# homeboard12.net
KiCad netlist of a schematic drawn in EAGLE
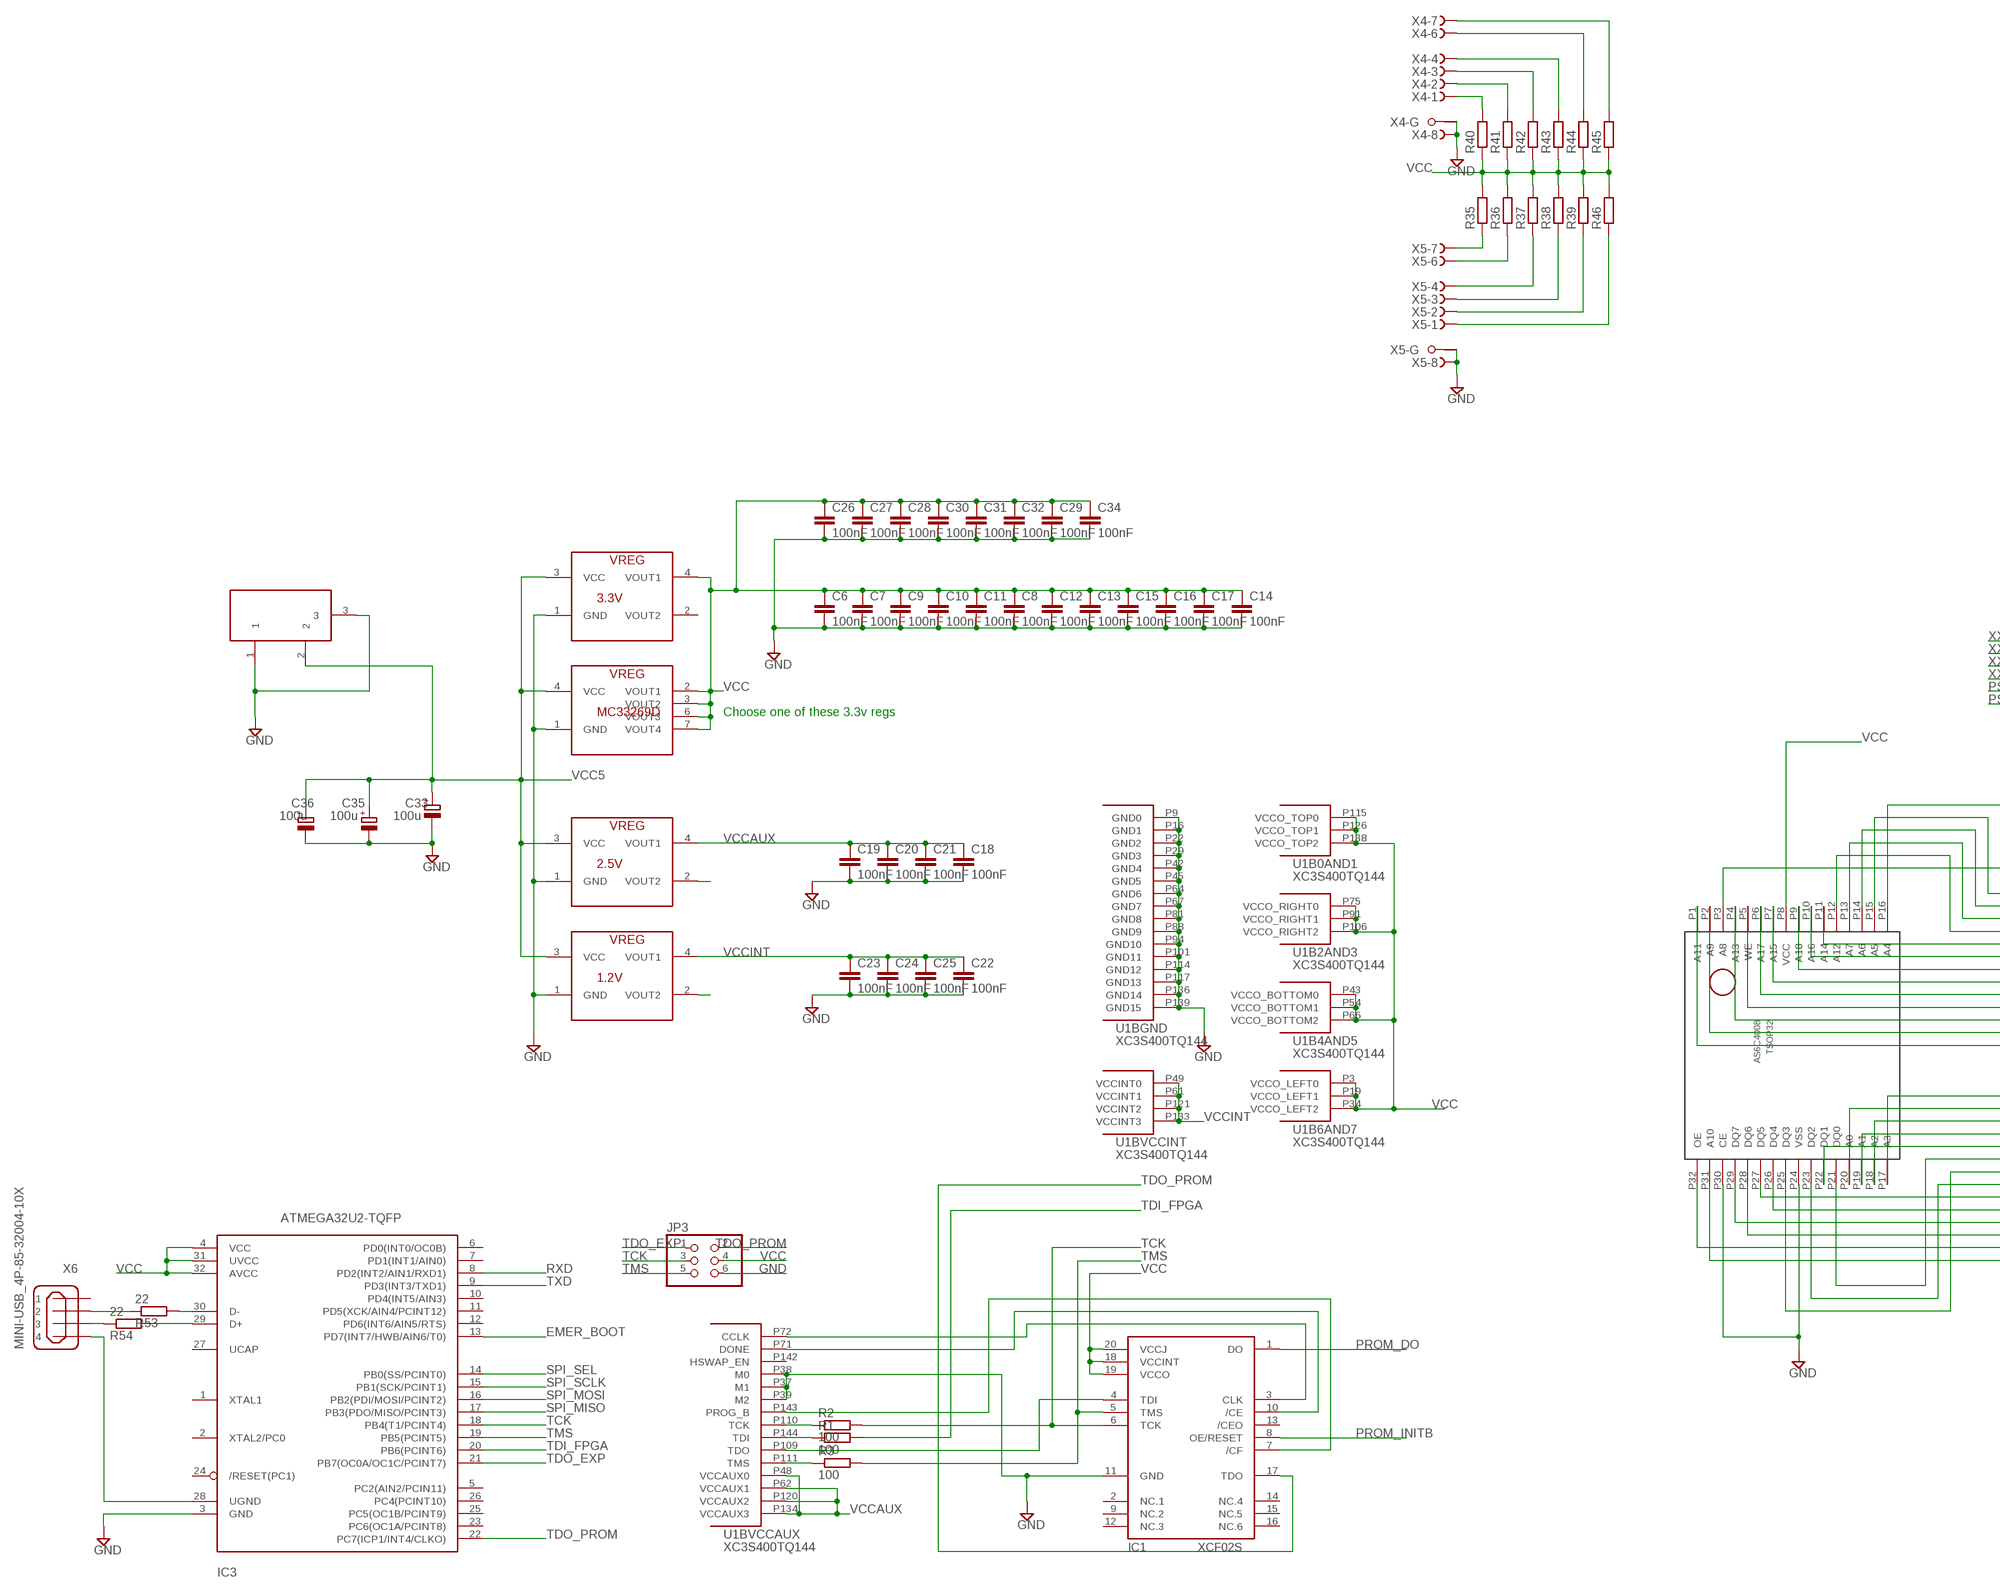
[diagram p0: schematic, sheet 1, part 1 of 3]
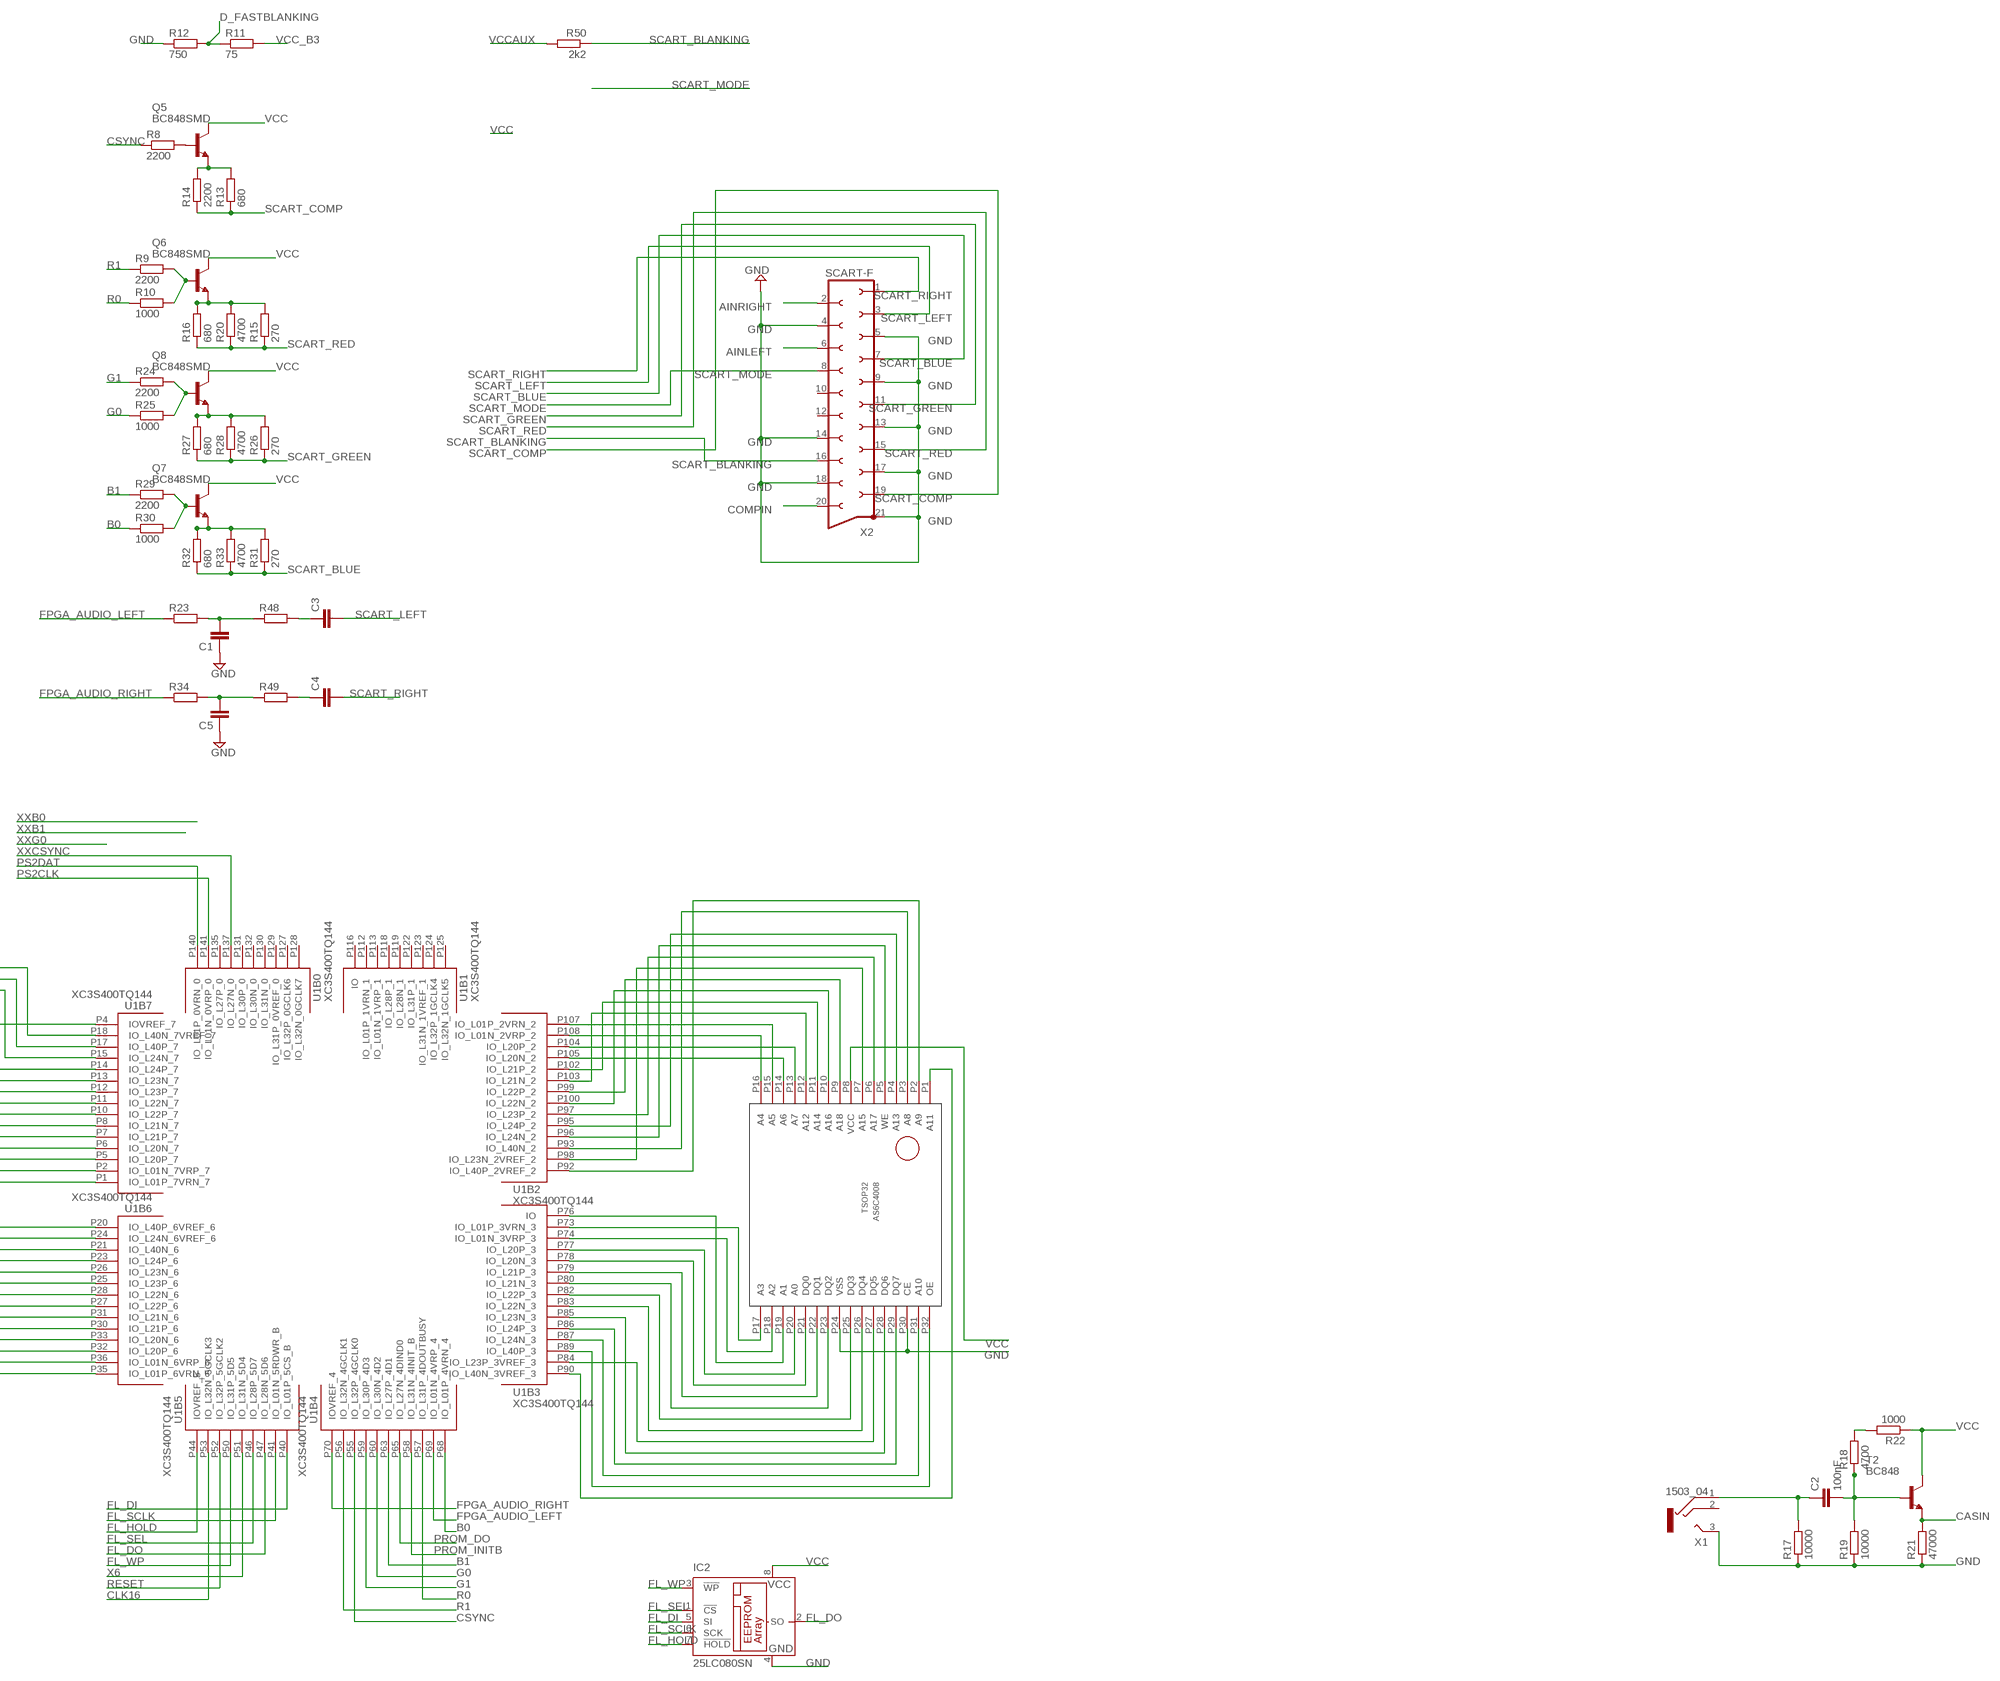
[diagram p1: schematic, sheet 1, part 2 of 3]
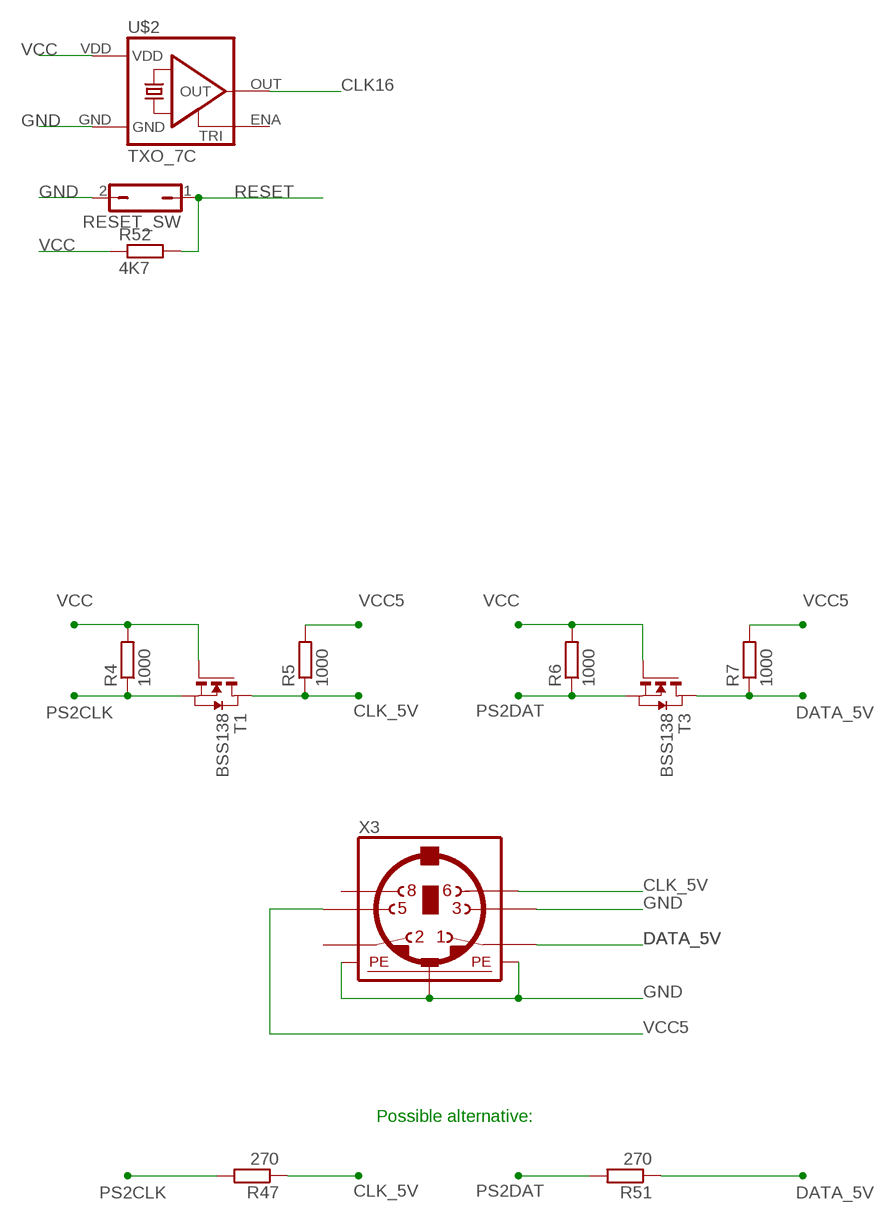
[diagram p2: schematic, sheet 1, part 3 of 3]

(export (version "E")
  (design (tool "Eeschema 10.0.6"))
  (components
    (comp (ref "C1")
      (value "C-EUC0603")
      (footprint "eagle-import:C0603")
      (libsource (lib "eagle-import") (part "resistor_C-EUC0603"))
    )
    (comp (ref "C2")
      (value "100nF")
      (footprint "eagle-import:C0603")
      (libsource (lib "eagle-import") (part "resistor_C-EUC0603"))
    )
    (comp (ref "C3")
      (value "C-EUC0603")
      (footprint "eagle-import:C0603")
      (libsource (lib "eagle-import") (part "resistor_C-EUC0603"))
    )
    (comp (ref "C4")
      (value "C-EUC0603")
      (footprint "eagle-import:C0603")
      (libsource (lib "eagle-import") (part "resistor_C-EUC0603"))
    )
    (comp (ref "C5")
      (value "C-EUC0603")
      (footprint "eagle-import:C0603")
      (libsource (lib "eagle-import") (part "resistor_C-EUC0603"))
    )
    (comp (ref "C6")
      (value "100nF")
      (footprint "eagle-import:C0603")
      (libsource (lib "eagle-import") (part "C-EUC0603"))
    )
    (comp (ref "C7")
      (value "100nF")
      (footprint "eagle-import:C0603")
      (libsource (lib "eagle-import") (part "C-EUC0603"))
    )
    (comp (ref "C8")
      (value "100nF")
      (footprint "eagle-import:C0603")
      (libsource (lib "eagle-import") (part "C-EUC0603"))
    )
    (comp (ref "C9")
      (value "100nF")
      (footprint "eagle-import:C0603")
      (libsource (lib "eagle-import") (part "C-EUC0603"))
    )
    (comp (ref "C10")
      (value "100nF")
      (footprint "eagle-import:C0603")
      (libsource (lib "eagle-import") (part "C-EUC0603"))
    )
    (comp (ref "C11")
      (value "100nF")
      (footprint "eagle-import:C0603")
      (libsource (lib "eagle-import") (part "C-EUC0603"))
    )
    (comp (ref "C12")
      (value "100nF")
      (footprint "eagle-import:C0603")
      (libsource (lib "eagle-import") (part "C-EUC0603"))
    )
    (comp (ref "C13")
      (value "100nF")
      (footprint "eagle-import:C0603")
      (libsource (lib "eagle-import") (part "C-EUC0603"))
    )
    (comp (ref "C14")
      (value "100nF")
      (footprint "eagle-import:C0603")
      (libsource (lib "eagle-import") (part "C-EUC0603"))
    )
    (comp (ref "C15")
      (value "100nF")
      (footprint "eagle-import:C0603")
      (libsource (lib "eagle-import") (part "C-EUC0603"))
    )
    (comp (ref "C16")
      (value "100nF")
      (footprint "eagle-import:C0603")
      (libsource (lib "eagle-import") (part "C-EUC0603"))
    )
    (comp (ref "C17")
      (value "100nF")
      (footprint "eagle-import:C0603")
      (libsource (lib "eagle-import") (part "C-EUC0603"))
    )
    (comp (ref "C18")
      (value "100nF")
      (footprint "eagle-import:C0603")
      (libsource (lib "eagle-import") (part "C-EUC0603"))
    )
    (comp (ref "C19")
      (value "100nF")
      (footprint "eagle-import:C0603")
      (libsource (lib "eagle-import") (part "C-EUC0603"))
    )
    (comp (ref "C20")
      (value "100nF")
      (footprint "eagle-import:C0603")
      (libsource (lib "eagle-import") (part "C-EUC0603"))
    )
    (comp (ref "C21")
      (value "100nF")
      (footprint "eagle-import:C0603")
      (libsource (lib "eagle-import") (part "C-EUC0603"))
    )
    (comp (ref "C22")
      (value "100nF")
      (footprint "eagle-import:C0603")
      (libsource (lib "eagle-import") (part "C-EUC0603"))
    )
    (comp (ref "C23")
      (value "100nF")
      (footprint "eagle-import:C0603")
      (libsource (lib "eagle-import") (part "C-EUC0603"))
    )
    (comp (ref "C24")
      (value "100nF")
      (footprint "eagle-import:C0603")
      (libsource (lib "eagle-import") (part "C-EUC0603"))
    )
    (comp (ref "C25")
      (value "100nF")
      (footprint "eagle-import:C0603")
      (libsource (lib "eagle-import") (part "C-EUC0603"))
    )
    (comp (ref "C26")
      (value "100nF")
      (footprint "eagle-import:C0603")
      (libsource (lib "eagle-import") (part "C-EUC0603"))
    )
    (comp (ref "C27")
      (value "100nF")
      (footprint "eagle-import:C0603")
      (libsource (lib "eagle-import") (part "C-EUC0603"))
    )
    (comp (ref "C28")
      (value "100nF")
      (footprint "eagle-import:C0603")
      (libsource (lib "eagle-import") (part "C-EUC0603"))
    )
    (comp (ref "C29")
      (value "100nF")
      (footprint "eagle-import:C0603")
      (libsource (lib "eagle-import") (part "C-EUC0603"))
    )
    (comp (ref "C30")
      (value "100nF")
      (footprint "eagle-import:C0603")
      (libsource (lib "eagle-import") (part "C-EUC0603"))
    )
    (comp (ref "C31")
      (value "100nF")
      (footprint "eagle-import:C0603")
      (libsource (lib "eagle-import") (part "C-EUC0603"))
    )
    (comp (ref "C32")
      (value "100nF")
      (footprint "eagle-import:C0603")
      (libsource (lib "eagle-import") (part "C-EUC0603"))
    )
    (comp (ref "C33")
      (value "100u")
      (footprint "eagle-import:PANASONIC_D")
      (libsource (lib "eagle-import") (part "CPOL-EUD"))
    )
    (comp (ref "C34")
      (value "100nF")
      (footprint "eagle-import:C0603")
      (libsource (lib "eagle-import") (part "C-EUC0603"))
    )
    (comp (ref "C35")
      (value "100u")
      (footprint "eagle-import:PANASONIC_D")
      (libsource (lib "eagle-import") (part "CPOL-EUD"))
    )
    (comp (ref "C36")
      (value "100u")
      (footprint "eagle-import:PANASONIC_D")
      (libsource (lib "eagle-import") (part "CPOL-EUD"))
    )
    (comp (ref "IC1")
      (value "XCF02S")
      (footprint "eagle-import:VO20")
      (libsource (lib "eagle-import") (part "XCF02S"))
    )
    (comp (ref "IC2")
      (value "25LC080SN")
      (footprint "eagle-import:SO-08")
      (fields (field (name "MF") "MICROCHIP") (field (name "MPN") "25LC080/SN"))
      (libsource (lib "eagle-import") (part "25SNLC080"))
    )
    (comp (ref "IC3")
      (value "ATMEGA32U2-TQFP")
      (footprint "eagle-import:TQFP32-08")
      (libsource (lib "eagle-import") (part "ATMEGA32U2-TQFP"))
    )
    (comp (ref "JP3")
      (value "PINHD-2X3")
      (footprint "eagle-import:2X03")
      (libsource (lib "eagle-import") (part "PINHD-2X3"))
    )
    (comp (ref "Q5")
      (value "BC848SMD")
      (footprint "eagle-import:SOT23")
      (libsource (lib "eagle-import") (part "BC848SMD"))
    )
    (comp (ref "Q6")
      (value "BC848SMD")
      (footprint "eagle-import:SOT23")
      (libsource (lib "eagle-import") (part "BC848SMD"))
    )
    (comp (ref "Q7")
      (value "BC848SMD")
      (footprint "eagle-import:SOT23")
      (libsource (lib "eagle-import") (part "BC848SMD"))
    )
    (comp (ref "Q8")
      (value "BC848SMD")
      (footprint "eagle-import:SOT23")
      (libsource (lib "eagle-import") (part "BC848SMD"))
    )
    (comp (ref "R1")
      (value "100")
      (footprint "eagle-import:R0805")
      (libsource (lib "eagle-import") (part "R-EU_R0805"))
    )
    (comp (ref "R2")
      (value "100")
      (footprint "eagle-import:R0805")
      (libsource (lib "eagle-import") (part "R-EU_R0805"))
    )
    (comp (ref "R3")
      (value "100")
      (footprint "eagle-import:R0805")
      (libsource (lib "eagle-import") (part "R-EU_R0805"))
    )
    (comp (ref "R4")
      (value "1000")
      (footprint "eagle-import:R0805")
      (libsource (lib "eagle-import") (part "R-EU_R0805"))
    )
    (comp (ref "R5")
      (value "1000")
      (footprint "eagle-import:R0805")
      (libsource (lib "eagle-import") (part "R-EU_R0805"))
    )
    (comp (ref "R6")
      (value "1000")
      (footprint "eagle-import:R0805")
      (libsource (lib "eagle-import") (part "R-EU_R0805"))
    )
    (comp (ref "R7")
      (value "1000")
      (footprint "eagle-import:R0805")
      (libsource (lib "eagle-import") (part "R-EU_R0805"))
    )
    (comp (ref "R8")
      (value "2200")
      (footprint "eagle-import:R0805")
      (libsource (lib "eagle-import") (part "R-EU_R0805"))
    )
    (comp (ref "R9")
      (value "2200")
      (footprint "eagle-import:R0805")
      (libsource (lib "eagle-import") (part "R-EU_R0805"))
    )
    (comp (ref "R10")
      (value "1000")
      (footprint "eagle-import:R0805")
      (libsource (lib "eagle-import") (part "R-EU_R0805"))
    )
    (comp (ref "R11")
      (value "75")
      (footprint "eagle-import:R0805")
      (libsource (lib "eagle-import") (part "R-EU_R0805"))
    )
    (comp (ref "R12")
      (value "750")
      (footprint "eagle-import:R0805")
      (libsource (lib "eagle-import") (part "R-EU_R0805"))
    )
    (comp (ref "R13")
      (value "680")
      (footprint "eagle-import:R0805")
      (libsource (lib "eagle-import") (part "R-EU_R0805"))
    )
    (comp (ref "R14")
      (value "2200")
      (footprint "eagle-import:R0805")
      (libsource (lib "eagle-import") (part "R-EU_R0805"))
    )
    (comp (ref "R15")
      (value "270")
      (footprint "eagle-import:R0805")
      (libsource (lib "eagle-import") (part "R-EU_R0805"))
    )
    (comp (ref "R16")
      (value "680")
      (footprint "eagle-import:R0805")
      (libsource (lib "eagle-import") (part "R-EU_R0805"))
    )
    (comp (ref "R17")
      (value "10000")
      (footprint "eagle-import:R0805")
      (libsource (lib "eagle-import") (part "R-EU_R0805"))
    )
    (comp (ref "R18")
      (value "4700")
      (footprint "eagle-import:R0805")
      (libsource (lib "eagle-import") (part "R-EU_R0805"))
    )
    (comp (ref "R19")
      (value "10000")
      (footprint "eagle-import:R0805")
      (libsource (lib "eagle-import") (part "R-EU_R0805"))
    )
    (comp (ref "R20")
      (value "4700")
      (footprint "eagle-import:R0805")
      (libsource (lib "eagle-import") (part "R-EU_R0805"))
    )
    (comp (ref "R21")
      (value "47000")
      (footprint "eagle-import:R0805")
      (libsource (lib "eagle-import") (part "R-EU_R0805"))
    )
    (comp (ref "R22")
      (value "1000")
      (footprint "eagle-import:R0805")
      (libsource (lib "eagle-import") (part "R-EU_R0805"))
    )
    (comp (ref "R23")
      (value "R-EU_M0805")
      (footprint "eagle-import:M0805")
      (libsource (lib "eagle-import") (part "resistor_R-EU_M0805"))
    )
    (comp (ref "R24")
      (value "2200")
      (footprint "eagle-import:R0805")
      (libsource (lib "eagle-import") (part "R-EU_R0805"))
    )
    (comp (ref "R25")
      (value "1000")
      (footprint "eagle-import:R0805")
      (libsource (lib "eagle-import") (part "R-EU_R0805"))
    )
    (comp (ref "R26")
      (value "270")
      (footprint "eagle-import:R0805")
      (libsource (lib "eagle-import") (part "R-EU_R0805"))
    )
    (comp (ref "R27")
      (value "680")
      (footprint "eagle-import:R0805")
      (libsource (lib "eagle-import") (part "R-EU_R0805"))
    )
    (comp (ref "R28")
      (value "4700")
      (footprint "eagle-import:R0805")
      (libsource (lib "eagle-import") (part "R-EU_R0805"))
    )
    (comp (ref "R29")
      (value "2200")
      (footprint "eagle-import:R0805")
      (libsource (lib "eagle-import") (part "R-EU_R0805"))
    )
    (comp (ref "R30")
      (value "1000")
      (footprint "eagle-import:R0805")
      (libsource (lib "eagle-import") (part "R-EU_R0805"))
    )
    (comp (ref "R31")
      (value "270")
      (footprint "eagle-import:R0805")
      (libsource (lib "eagle-import") (part "R-EU_R0805"))
    )
    (comp (ref "R32")
      (value "680")
      (footprint "eagle-import:R0805")
      (libsource (lib "eagle-import") (part "R-EU_R0805"))
    )
    (comp (ref "R33")
      (value "4700")
      (footprint "eagle-import:R0805")
      (libsource (lib "eagle-import") (part "R-EU_R0805"))
    )
    (comp (ref "R34")
      (value "R-EU_M0805")
      (footprint "eagle-import:M0805")
      (libsource (lib "eagle-import") (part "resistor_R-EU_M0805"))
    )
    (comp (ref "R35")
      (value "R-EU_M0805")
      (footprint "eagle-import:M0805")
      (libsource (lib "eagle-import") (part "resistor_R-EU_M0805"))
    )
    (comp (ref "R36")
      (value "R-EU_M0805")
      (footprint "eagle-import:M0805")
      (libsource (lib "eagle-import") (part "resistor_R-EU_M0805"))
    )
    (comp (ref "R37")
      (value "R-EU_M0805")
      (footprint "eagle-import:M0805")
      (libsource (lib "eagle-import") (part "resistor_R-EU_M0805"))
    )
    (comp (ref "R38")
      (value "R-EU_M0805")
      (footprint "eagle-import:M0805")
      (libsource (lib "eagle-import") (part "resistor_R-EU_M0805"))
    )
    (comp (ref "R39")
      (value "R-EU_M0805")
      (footprint "eagle-import:M0805")
      (libsource (lib "eagle-import") (part "resistor_R-EU_M0805"))
    )
    (comp (ref "R40")
      (value "R-EU_M0805")
      (footprint "eagle-import:M0805")
      (libsource (lib "eagle-import") (part "resistor_R-EU_M0805"))
    )
    (comp (ref "R41")
      (value "R-EU_M0805")
      (footprint "eagle-import:M0805")
      (libsource (lib "eagle-import") (part "resistor_R-EU_M0805"))
    )
    (comp (ref "R42")
      (value "R-EU_M0805")
      (footprint "eagle-import:M0805")
      (libsource (lib "eagle-import") (part "resistor_R-EU_M0805"))
    )
    (comp (ref "R43")
      (value "R-EU_M0805")
      (footprint "eagle-import:M0805")
      (libsource (lib "eagle-import") (part "resistor_R-EU_M0805"))
    )
    (comp (ref "R44")
      (value "R-EU_M0805")
      (footprint "eagle-import:M0805")
      (libsource (lib "eagle-import") (part "resistor_R-EU_M0805"))
    )
    (comp (ref "R45")
      (value "R-EU_M0805")
      (footprint "eagle-import:M0805")
      (libsource (lib "eagle-import") (part "resistor_R-EU_M0805"))
    )
    (comp (ref "R46")
      (value "R-EU_M0805")
      (footprint "eagle-import:M0805")
      (libsource (lib "eagle-import") (part "resistor_R-EU_M0805"))
    )
    (comp (ref "R47")
      (value "270")
      (footprint "eagle-import:R0805")
      (libsource (lib "eagle-import") (part "R-EU_R0805"))
    )
    (comp (ref "R48")
      (value "R-EU_M0805")
      (footprint "eagle-import:M0805")
      (libsource (lib "eagle-import") (part "resistor_R-EU_M0805"))
    )
    (comp (ref "R49")
      (value "R-EU_M0805")
      (footprint "eagle-import:M0805")
      (libsource (lib "eagle-import") (part "resistor_R-EU_M0805"))
    )
    (comp (ref "R50")
      (value "2k2")
      (footprint "eagle-import:M0805")
      (libsource (lib "eagle-import") (part "resistor_R-EU_M0805"))
    )
    (comp (ref "R51")
      (value "270")
      (footprint "eagle-import:R0805")
      (libsource (lib "eagle-import") (part "R-EU_R0805"))
    )
    (comp (ref "R52")
      (value "4K7")
      (footprint "eagle-import:M0805")
      (libsource (lib "eagle-import") (part "resistor_R-EU_M0805"))
    )
    (comp (ref "R53")
      (value "22")
      (footprint "eagle-import:R0805")
      (libsource (lib "eagle-import") (part "R-EU_R0805"))
    )
    (comp (ref "R54")
      (value "22")
      (footprint "eagle-import:R0805")
      (libsource (lib "eagle-import") (part "R-EU_R0805"))
    )
    (comp (ref "REG1.2")
      (value "1.2V")
      (footprint "eagle-import:SOT223")
      (libsource (lib "eagle-import") (part "NX1117"))
    )
    (comp (ref "REG2.5")
      (value "2.5V")
      (footprint "eagle-import:SOT223")
      (libsource (lib "eagle-import") (part "NX1117"))
    )
    (comp (ref "RESET_SW")
      (value "JP1Q")
      (footprint "eagle-import:JP1")
      (libsource (lib "eagle-import") (part "JP1Q"))
    )
    (comp (ref "T1")
      (value "BSS138")
      (footprint "eagle-import:SOT-23")
      (libsource (lib "eagle-import") (part "NMOSSOT23"))
    )
    (comp (ref "T2")
      (value "BC848")
      (footprint "eagle-import:SOT23")
      (libsource (lib "eagle-import") (part "BC848"))
    )
    (comp (ref "T3")
      (value "BSS138")
      (footprint "eagle-import:SOT-23")
      (libsource (lib "eagle-import") (part "NMOSSOT23"))
    )
    (comp (ref "U$1")
      (value "AS6C4008")
      (footprint "eagle-import:TSOP32")
      (libsource (lib "eagle-import") (part "AS6C4008"))
    )
    (comp (ref "U$2")
      (value "TXO_7C")
      (footprint "eagle-import:OSC_7C")
      (libsource (lib "eagle-import") (part "TXO_7C"))
    )
    (comp (ref "U$4")
      (value "3.3V")
      (footprint "eagle-import:SOT223")
      (libsource (lib "eagle-import") (part "NX1117"))
    )
    (comp (ref "U$5")
      (value "MC33269D")
      (footprint "eagle-import:SO8")
      (libsource (lib "eagle-import") (part "MC33269D"))
    )
    (comp (ref "U$6")
      (value "AS6C4008")
      (footprint "eagle-import:TSOP32")
      (libsource (lib "eagle-import") (part "AS6C4008"))
    )
    (comp (ref "U1")
      (value "XC3S400TQ144")
      (footprint "eagle-import:TQ144")
      (libsource (lib "eagle-import") (part "XC3S400TQ144"))
    )
    (comp (ref "X1")
      (value "1503_04")
      (footprint "eagle-import:1503_04")
      (libsource (lib "eagle-import") (part "1503_04"))
    )
    (comp (ref "X2")
      (value "SCART-F")
      (footprint "eagle-import:SCART-F")
      (libsource (lib "eagle-import") (part "SCART-F"))
    )
    (comp (ref "X3")
      (value "MINI_DIN_6")
      (footprint "eagle-import:M_DIN6")
      (libsource (lib "eagle-import") (part "MINI_DIN_6"))
    )
    (comp (ref "X4")
      (value "F09HPS")
      (footprint "eagle-import:F09HP")
      (libsource (lib "eagle-import") (part "F09HPS"))
    )
    (comp (ref "X5")
      (value "F09HPS")
      (footprint "eagle-import:F09HP")
      (libsource (lib "eagle-import") (part "F09HPS"))
    )
    (comp (ref "X6")
      (value "MINI-USB_4P-85-32004-10X")
      (footprint "eagle-import:85-32004-10X")
      (libsource (lib "eagle-import") (part "MINI-USB_4P-85-32004-10X"))
    )
    (comp (ref "X8")
      (value "DC21MMX")
      (footprint "eagle-import:DC-21MM")
      (libsource (lib "eagle-import") (part "DC21MMX"))
    )
  )
  (nets
    (net (code "1") (name "/AINLEFT") (class "Default")
      (node (ref "X2") (pin "6") (pinfunction "6_6") (pintype "passive"))
    )
    (net (code "2") (name "/AINRIGHT") (class "Default")
      (node (ref "X2") (pin "2") (pinfunction "2_2") (pintype "passive"))
    )
    (net (code "3") (name "/B0") (class "Default")
      (node (ref "R30") (pin "1") (pinfunction "1_1") (pintype "passive"))
      (node (ref "U1") (pin "P68") (pinfunction "IO_L01P_4VRN_4_P68") (pintype "bidirectional"))
    )
    (net (code "4") (name "/B1") (class "Default")
      (node (ref "R29") (pin "1") (pinfunction "1_1") (pintype "passive"))
      (node (ref "U1") (pin "P63") (pinfunction "IO_L27P_4D1_P63") (pintype "bidirectional"))
    )
    (net (code "5") (name "/CASIN") (class "Default")
      (node (ref "R21") (pin "2") (pinfunction "2_2") (pintype "passive"))
      (node (ref "T2") (pin "2") (pinfunction "E_2") (pintype "passive"))
    )
    (net (code "6") (name "/CLK16") (class "Default")
      (node (ref "U$2") (pin "OUT") (pinfunction "OUT_OUT") (pintype "output"))
      (node (ref "U1") (pin "P53") (pinfunction "IO_L32N_5GCLK3_P53") (pintype "bidirectional"))
    )
    (net (code "7") (name "/CLK_5V") (class "Default")
      (node (ref "R47") (pin "1") (pinfunction "1_1") (pintype "passive"))
      (node (ref "R5") (pin "1") (pinfunction "1_1") (pintype "passive"))
      (node (ref "T1") (pin "1") (pinfunction "D_1") (pintype "passive"))
      (node (ref "X3") (pin "6") (pinfunction "6_6") (pintype "passive"))
    )
    (net (code "8") (name "/COMPIN") (class "Default")
      (node (ref "X2") (pin "20") (pinfunction "20_20") (pintype "passive"))
    )
    (net (code "9") (name "/CSYNC") (class "Default")
      (node (ref "R8") (pin "1") (pinfunction "1_1") (pintype "passive"))
      (node (ref "U1") (pin "P55") (pinfunction "IO_L32P_4GCLK0_P55") (pintype "bidirectional"))
    )
    (net (code "10") (name "/DATA_5V") (class "Default")
      (node (ref "R51") (pin "1") (pinfunction "1_1") (pintype "passive"))
      (node (ref "R7") (pin "1") (pinfunction "1_1") (pintype "passive"))
      (node (ref "T3") (pin "1") (pinfunction "D_1") (pintype "passive"))
      (node (ref "X3") (pin "1") (pinfunction "1_1") (pintype "passive"))
    )
    (net (code "11") (name "/D_FASTBLANKING") (class "Default")
      (node (ref "R11") (pin "1") (pinfunction "1_1") (pintype "passive"))
      (node (ref "R12") (pin "2") (pinfunction "2_2") (pintype "passive"))
    )
    (net (code "12") (name "/EMER_BOOT") (class "Default")
      (node (ref "IC3") (pin "13") (pinfunction "PD7(INT7/HWB/AIN6/T0)_13") (pintype "bidirectional"))
    )
    (net (code "13") (name "/FL_DI") (class "Default")
      (node (ref "IC2") (pin "5") (pinfunction "SI_5") (pintype "input"))
      (node (ref "U1") (pin "P40") (pinfunction "IO_L01P_5CS_B_P40") (pintype "bidirectional"))
    )
    (net (code "14") (name "/FL_DO") (class "Default")
      (node (ref "IC2") (pin "2") (pinfunction "SO_2") (pintype "bidirectional"))
      (node (ref "U1") (pin "P47") (pinfunction "IO_L28N_5D6_P47") (pintype "bidirectional"))
    )
    (net (code "15") (name "/FL_HOLD") (class "Default")
      (node (ref "IC2") (pin "7") (pinfunction "~{HOLD}_7") (pintype "input"))
      (node (ref "U1") (pin "P44") (pinfunction "IOVREF_5_P44") (pintype "bidirectional"))
    )
    (net (code "16") (name "/FL_SCLK") (class "Default")
      (node (ref "IC2") (pin "6") (pinfunction "SCK_6") (pintype "input"))
      (node (ref "U1") (pin "P41") (pinfunction "IO_L01N_5RDWR_B_P41") (pintype "bidirectional"))
    )
    (net (code "17") (name "/FL_SEL") (class "Default")
      (node (ref "IC2") (pin "1") (pinfunction "~{CS}_1") (pintype "input"))
      (node (ref "U1") (pin "P46") (pinfunction "IO_L28P_5D7_P46") (pintype "bidirectional"))
    )
    (net (code "18") (name "/FL_WP") (class "Default")
      (node (ref "IC2") (pin "3") (pinfunction "~{WP}_3") (pintype "input"))
      (node (ref "U1") (pin "P50") (pinfunction "IO_L31P_5D5_P50") (pintype "bidirectional"))
    )
    (net (code "19") (name "/FPGA_AUDIO_LEFT") (class "Default")
      (node (ref "R23") (pin "1") (pinfunction "1_1") (pintype "passive"))
      (node (ref "U1") (pin "P69") (pinfunction "IO_L01N_4VRP_4_P69") (pintype "bidirectional"))
    )
    (net (code "20") (name "/FPGA_AUDIO_RIGHT") (class "Default")
      (node (ref "R34") (pin "1") (pinfunction "1_1") (pintype "passive"))
      (node (ref "U1") (pin "P70") (pinfunction "IOVREF_4_P70") (pintype "bidirectional"))
    )
    (net (code "21") (name "/G0") (class "Default")
      (node (ref "R25") (pin "1") (pinfunction "1_1") (pintype "passive"))
      (node (ref "U1") (pin "P60") (pinfunction "IO_L30N_4D2_P60") (pintype "bidirectional"))
    )
    (net (code "22") (name "/G1") (class "Default")
      (node (ref "R24") (pin "1") (pinfunction "1_1") (pintype "passive"))
      (node (ref "U1") (pin "P59") (pinfunction "IO_L30P_4D3_P59") (pintype "bidirectional"))
    )
    (net (code "23") (name "/PROM_DO") (class "Default")
      (node (ref "IC1") (pin "1") (pinfunction "DO_1") (pintype "bidirectional"))
      (node (ref "U1") (pin "P65") (pinfunction "IO_L27N_4DIND0_P65") (pintype "bidirectional"))
    )
    (net (code "24") (name "/PROM_INITB") (class "Default")
      (node (ref "IC1") (pin "8") (pinfunction "OE/RESET_8") (pintype "bidirectional"))
      (node (ref "U1") (pin "P58") (pinfunction "IO_L31N_4INIT_B_P58") (pintype "bidirectional"))
    )
    (net (code "25") (name "/PS2CLK") (class "Default")
      (node (ref "R4") (pin "1") (pinfunction "1_1") (pintype "passive"))
      (node (ref "R47") (pin "2") (pinfunction "2_2") (pintype "passive"))
      (node (ref "T1") (pin "2") (pinfunction "S_2") (pintype "passive"))
      (node (ref "U1") (pin "P141") (pinfunction "IO_L01N_0VRP_0_P141") (pintype "bidirectional"))
    )
    (net (code "26") (name "/PS2DAT") (class "Default")
      (node (ref "R51") (pin "2") (pinfunction "2_2") (pintype "passive"))
      (node (ref "R6") (pin "1") (pinfunction "1_1") (pintype "passive"))
      (node (ref "T3") (pin "2") (pinfunction "S_2") (pintype "passive"))
      (node (ref "U1") (pin "P140") (pinfunction "IO_L01P_0VRN_0_P140") (pintype "bidirectional"))
    )
    (net (code "27") (name "/R0") (class "Default")
      (node (ref "R10") (pin "1") (pinfunction "1_1") (pintype "passive"))
      (node (ref "U1") (pin "P57") (pinfunction "IO_L31P_4DOUTBUSY_P57") (pintype "bidirectional"))
    )
    (net (code "28") (name "/R1") (class "Default")
      (node (ref "R9") (pin "1") (pinfunction "1_1") (pintype "passive"))
      (node (ref "U1") (pin "P56") (pinfunction "IO_L32N_4GCLK1_P56") (pintype "bidirectional"))
    )
    (net (code "29") (name "/RESET") (class "Default")
      (node (ref "R52") (pin "2") (pinfunction "2_2") (pintype "passive"))
      (node (ref "RESET_SW") (pin "1") (pinfunction "1_1") (pintype "passive"))
      (node (ref "U1") (pin "P52") (pinfunction "IO_L32P_5GCLK2_P52") (pintype "bidirectional"))
    )
    (net (code "30") (name "/RXD") (class "Default")
      (node (ref "IC3") (pin "8") (pinfunction "PD2(INT2/AIN1/RXD1)_8") (pintype "bidirectional"))
    )
    (net (code "31") (name "/SCART_BLANKING") (class "Default")
      (node (ref "R50") (pin "1") (pinfunction "1_1") (pintype "passive"))
      (node (ref "X2") (pin "16") (pinfunction "16_16") (pintype "passive"))
    )
    (net (code "32") (name "/SCART_BLUE") (class "Default")
      (node (ref "R31") (pin "1") (pinfunction "1_1") (pintype "passive"))
      (node (ref "R32") (pin "1") (pinfunction "1_1") (pintype "passive"))
      (node (ref "R33") (pin "1") (pinfunction "1_1") (pintype "passive"))
      (node (ref "X2") (pin "7") (pinfunction "7_7") (pintype "passive"))
    )
    (net (code "33") (name "/SCART_COMP") (class "Default")
      (node (ref "R13") (pin "1") (pinfunction "1_1") (pintype "passive"))
      (node (ref "R14") (pin "1") (pinfunction "1_1") (pintype "passive"))
      (node (ref "X2") (pin "19") (pinfunction "19_19") (pintype "passive"))
    )
    (net (code "34") (name "/SCART_GREEN") (class "Default")
      (node (ref "R26") (pin "1") (pinfunction "1_1") (pintype "passive"))
      (node (ref "R27") (pin "1") (pinfunction "1_1") (pintype "passive"))
      (node (ref "R28") (pin "1") (pinfunction "1_1") (pintype "passive"))
      (node (ref "X2") (pin "11") (pinfunction "11_11") (pintype "passive"))
    )
    (net (code "35") (name "/SCART_LEFT") (class "Default")
      (node (ref "C3") (pin "2") (pinfunction "2_2") (pintype "passive"))
      (node (ref "X2") (pin "3") (pinfunction "3_3") (pintype "passive"))
    )
    (net (code "36") (name "/SCART_MODE") (class "Default")
      (node (ref "X2") (pin "8") (pinfunction "8_8") (pintype "passive"))
    )
    (net (code "37") (name "/SCART_RED") (class "Default")
      (node (ref "R15") (pin "1") (pinfunction "1_1") (pintype "passive"))
      (node (ref "R16") (pin "1") (pinfunction "1_1") (pintype "passive"))
      (node (ref "R20") (pin "1") (pinfunction "1_1") (pintype "passive"))
      (node (ref "X2") (pin "15") (pinfunction "15_15") (pintype "passive"))
    )
    (net (code "38") (name "/SCART_RIGHT") (class "Default")
      (node (ref "C4") (pin "2") (pinfunction "2_2") (pintype "passive"))
      (node (ref "X2") (pin "1") (pinfunction "1_1") (pintype "passive"))
    )
    (net (code "39") (name "/SPI_MISO") (class "Default")
      (node (ref "IC3") (pin "17") (pinfunction "PB3(PDO/MISO/PCINT3)_17") (pintype "bidirectional"))
    )
    (net (code "40") (name "/SPI_MOSI") (class "Default")
      (node (ref "IC3") (pin "16") (pinfunction "PB2(PDI/MOSI/PCINT2)_16") (pintype "bidirectional"))
    )
    (net (code "41") (name "/SPI_SCLK") (class "Default")
      (node (ref "IC3") (pin "15") (pinfunction "PB1(SCK/PCINT1)_15") (pintype "bidirectional"))
    )
    (net (code "42") (name "/SPI_SEL") (class "Default")
      (node (ref "IC3") (pin "14") (pinfunction "PB0(SS/PCINT0)_14") (pintype "bidirectional"))
    )
    (net (code "43") (name "/TCK") (class "Default")
      (node (ref "IC1") (pin "6") (pinfunction "TCK_6") (pintype "bidirectional"))
      (node (ref "IC3") (pin "18") (pinfunction "PB4(T1/PCINT4)_18") (pintype "bidirectional"))
      (node (ref "JP3") (pin "3") (pinfunction "3_3") (pintype "passive"))
      (node (ref "R2") (pin "2") (pinfunction "2_2") (pintype "passive"))
    )
    (net (code "44") (name "/TDI_FPGA") (class "Default")
      (node (ref "IC3") (pin "20") (pinfunction "PB6(PCINT6)_20") (pintype "bidirectional"))
      (node (ref "R1") (pin "2") (pinfunction "2_2") (pintype "passive"))
    )
    (net (code "45") (name "/TDO_EXP") (class "Default")
      (node (ref "IC3") (pin "21") (pinfunction "PB7(OC0A/OC1C/PCINT7)_21") (pintype "bidirectional"))
      (node (ref "JP3") (pin "1") (pinfunction "1_1") (pintype "passive"))
    )
    (net (code "46") (name "/TDO_PROM") (class "Default")
      (node (ref "IC1") (pin "17") (pinfunction "TDO_17") (pintype "bidirectional"))
      (node (ref "IC3") (pin "22") (pinfunction "PC7(ICP1/INT4/CLKO)_22") (pintype "bidirectional"))
      (node (ref "JP3") (pin "2") (pinfunction "2_2") (pintype "passive"))
    )
    (net (code "47") (name "/TMS") (class "Default")
      (node (ref "IC1") (pin "5") (pinfunction "TMS_5") (pintype "bidirectional"))
      (node (ref "IC3") (pin "19") (pinfunction "PB5(PCINT5)_19") (pintype "bidirectional"))
      (node (ref "JP3") (pin "5") (pinfunction "5_5") (pintype "passive"))
      (node (ref "R3") (pin "2") (pinfunction "2_2") (pintype "passive"))
    )
    (net (code "48") (name "/TXD") (class "Default")
      (node (ref "IC3") (pin "9") (pinfunction "PD3(INT3/TXD1)_9") (pintype "bidirectional"))
    )
    (net (code "49") (name "/VCC") (class "Default")
      (node (ref "C10") (pin "1") (pinfunction "1_1") (pintype "passive"))
      (node (ref "C11") (pin "1") (pinfunction "1_1") (pintype "passive"))
      (node (ref "C12") (pin "1") (pinfunction "1_1") (pintype "passive"))
      (node (ref "C13") (pin "1") (pinfunction "1_1") (pintype "passive"))
      (node (ref "C14") (pin "1") (pinfunction "1_1") (pintype "passive"))
      (node (ref "C15") (pin "1") (pinfunction "1_1") (pintype "passive"))
      (node (ref "C16") (pin "1") (pinfunction "1_1") (pintype "passive"))
      (node (ref "C17") (pin "1") (pinfunction "1_1") (pintype "passive"))
      (node (ref "C26") (pin "1") (pinfunction "1_1") (pintype "passive"))
      (node (ref "C27") (pin "1") (pinfunction "1_1") (pintype "passive"))
      (node (ref "C28") (pin "1") (pinfunction "1_1") (pintype "passive"))
      (node (ref "C29") (pin "1") (pinfunction "1_1") (pintype "passive"))
      (node (ref "C30") (pin "1") (pinfunction "1_1") (pintype "passive"))
      (node (ref "C31") (pin "1") (pinfunction "1_1") (pintype "passive"))
      (node (ref "C32") (pin "1") (pinfunction "1_1") (pintype "passive"))
      (node (ref "C34") (pin "1") (pinfunction "1_1") (pintype "passive"))
      (node (ref "C6") (pin "1") (pinfunction "1_1") (pintype "passive"))
      (node (ref "C7") (pin "1") (pinfunction "1_1") (pintype "passive"))
      (node (ref "C8") (pin "1") (pinfunction "1_1") (pintype "passive"))
      (node (ref "C9") (pin "1") (pinfunction "1_1") (pintype "passive"))
      (node (ref "IC1") (pin "18") (pinfunction "VCCINT_18") (pintype "bidirectional"))
      (node (ref "IC1") (pin "19") (pinfunction "VCCO_19") (pintype "bidirectional"))
      (node (ref "IC1") (pin "20") (pinfunction "VCCJ_20") (pintype "bidirectional"))
      (node (ref "IC2") (pin "8") (pinfunction "VCC_8") (pintype "power_in"))
      (node (ref "IC3") (pin "31") (pinfunction "UVCC_31") (pintype "bidirectional"))
      (node (ref "IC3") (pin "32") (pinfunction "AVCC_32") (pintype "bidirectional"))
      (node (ref "IC3") (pin "4") (pinfunction "VCC_4") (pintype "bidirectional"))
      (node (ref "JP3") (pin "4") (pinfunction "4_4") (pintype "passive"))
      (node (ref "Q5") (pin "3") (pinfunction "C_3") (pintype "passive"))
      (node (ref "Q6") (pin "3") (pinfunction "C_3") (pintype "passive"))
      (node (ref "Q7") (pin "3") (pinfunction "C_3") (pintype "passive"))
      (node (ref "Q8") (pin "3") (pinfunction "C_3") (pintype "passive"))
      (node (ref "R22") (pin "1") (pinfunction "1_1") (pintype "passive"))
      (node (ref "R35") (pin "2") (pinfunction "2_2") (pintype "passive"))
      (node (ref "R36") (pin "2") (pinfunction "2_2") (pintype "passive"))
      (node (ref "R37") (pin "2") (pinfunction "2_2") (pintype "passive"))
      (node (ref "R38") (pin "2") (pinfunction "2_2") (pintype "passive"))
      (node (ref "R39") (pin "2") (pinfunction "2_2") (pintype "passive"))
      (node (ref "R4") (pin "2") (pinfunction "2_2") (pintype "passive"))
      (node (ref "R40") (pin "1") (pinfunction "1_1") (pintype "passive"))
      (node (ref "R41") (pin "1") (pinfunction "1_1") (pintype "passive"))
      (node (ref "R42") (pin "1") (pinfunction "1_1") (pintype "passive"))
      (node (ref "R43") (pin "1") (pinfunction "1_1") (pintype "passive"))
      (node (ref "R44") (pin "1") (pinfunction "1_1") (pintype "passive"))
      (node (ref "R45") (pin "1") (pinfunction "1_1") (pintype "passive"))
      (node (ref "R46") (pin "2") (pinfunction "2_2") (pintype "passive"))
      (node (ref "R52") (pin "1") (pinfunction "1_1") (pintype "passive"))
      (node (ref "R6") (pin "2") (pinfunction "2_2") (pintype "passive"))
      (node (ref "T1") (pin "3") (pinfunction "G_3") (pintype "passive"))
      (node (ref "T2") (pin "3") (pinfunction "C_3") (pintype "passive"))
      (node (ref "T3") (pin "3") (pinfunction "G_3") (pintype "passive"))
      (node (ref "U$1") (pin "P8") (pinfunction "VCC_P8") (pintype "bidirectional"))
      (node (ref "U$2") (pin "VDD") (pinfunction "VDD_VDD") (pintype "power_in"))
      (node (ref "U$4") (pin "4") (pinfunction "VOUT1_4") (pintype "bidirectional"))
      (node (ref "U$5") (pin "2") (pinfunction "VOUT1_2") (pintype "output"))
      (node (ref "U$5") (pin "3") (pinfunction "VOUT2_3") (pintype "output"))
      (node (ref "U$5") (pin "6") (pinfunction "VOUT3_6") (pintype "output"))
      (node (ref "U$5") (pin "7") (pinfunction "VOUT4_7") (pintype "output"))
      (node (ref "U$6") (pin "P8") (pinfunction "VCC_P8") (pintype "bidirectional"))
      (node (ref "U1") (pin "P106") (pinfunction "VCCO_RIGHT2_P106") (pintype "passive"))
      (node (ref "U1") (pin "P115") (pinfunction "VCCO_TOP0_P115") (pintype "passive"))
      (node (ref "U1") (pin "P126") (pinfunction "VCCO_TOP1_P126") (pintype "passive"))
      (node (ref "U1") (pin "P138") (pinfunction "VCCO_TOP2_P138") (pintype "passive"))
      (node (ref "U1") (pin "P19") (pinfunction "VCCO_LEFT1_P19") (pintype "passive"))
      (node (ref "U1") (pin "P3") (pinfunction "VCCO_LEFT0_P3") (pintype "passive"))
      (node (ref "U1") (pin "P34") (pinfunction "VCCO_LEFT2_P34") (pintype "passive"))
      (node (ref "U1") (pin "P43") (pinfunction "VCCO_BOTTOM0_P43") (pintype "passive"))
      (node (ref "U1") (pin "P54") (pinfunction "VCCO_BOTTOM1_P54") (pintype "passive"))
      (node (ref "U1") (pin "P66") (pinfunction "VCCO_BOTTOM2_P66") (pintype "passive"))
      (node (ref "U1") (pin "P75") (pinfunction "VCCO_RIGHT0_P75") (pintype "passive"))
      (node (ref "U1") (pin "P91") (pinfunction "VCCO_RIGHT1_P91") (pintype "passive"))
    )
    (net (code "50") (name "/VCC5") (class "Default")
      (node (ref "C33") (pin "+") (pinfunction "+_+") (pintype "passive"))
      (node (ref "C35") (pin "+") (pinfunction "+_+") (pintype "passive"))
      (node (ref "C36") (pin "+") (pinfunction "+_+") (pintype "passive"))
      (node (ref "R5") (pin "2") (pinfunction "2_2") (pintype "passive"))
      (node (ref "R7") (pin "2") (pinfunction "2_2") (pintype "passive"))
      (node (ref "REG1.2") (pin "3") (pinfunction "VCC_3") (pintype "bidirectional"))
      (node (ref "REG2.5") (pin "3") (pinfunction "VCC_3") (pintype "bidirectional"))
      (node (ref "U$4") (pin "3") (pinfunction "VCC_3") (pintype "bidirectional"))
      (node (ref "U$5") (pin "4") (pinfunction "VCC_4") (pintype "bidirectional"))
      (node (ref "X3") (pin "5") (pinfunction "5_5") (pintype "passive"))
      (node (ref "X8") (pin "2") (pinfunction "2_2") (pintype "power_in"))
    )
    (net (code "51") (name "/VCCAUX") (class "Default")
      (node (ref "C18") (pin "1") (pinfunction "1_1") (pintype "passive"))
      (node (ref "C19") (pin "1") (pinfunction "1_1") (pintype "passive"))
      (node (ref "C20") (pin "1") (pinfunction "1_1") (pintype "passive"))
      (node (ref "C21") (pin "1") (pinfunction "1_1") (pintype "passive"))
      (node (ref "R50") (pin "2") (pinfunction "2_2") (pintype "passive"))
      (node (ref "REG2.5") (pin "4") (pinfunction "VOUT1_4") (pintype "bidirectional"))
      (node (ref "U1") (pin "P120") (pinfunction "VCCAUX2_P120") (pintype "passive"))
      (node (ref "U1") (pin "P134") (pinfunction "VCCAUX3_P134") (pintype "passive"))
      (node (ref "U1") (pin "P48") (pinfunction "VCCAUX0_P48") (pintype "passive"))
      (node (ref "U1") (pin "P62") (pinfunction "VCCAUX1_P62") (pintype "passive"))
    )
    (net (code "52") (name "/VCCINT") (class "Default")
      (node (ref "C22") (pin "1") (pinfunction "1_1") (pintype "passive"))
      (node (ref "C23") (pin "1") (pinfunction "1_1") (pintype "passive"))
      (node (ref "C24") (pin "1") (pinfunction "1_1") (pintype "passive"))
      (node (ref "C25") (pin "1") (pinfunction "1_1") (pintype "passive"))
      (node (ref "REG1.2") (pin "4") (pinfunction "VOUT1_4") (pintype "bidirectional"))
      (node (ref "U1") (pin "P121") (pinfunction "VCCINT2_P121") (pintype "passive"))
      (node (ref "U1") (pin "P133") (pinfunction "VCCINT3_P133") (pintype "passive"))
      (node (ref "U1") (pin "P49") (pinfunction "VCCINT0_P49") (pintype "passive"))
      (node (ref "U1") (pin "P61") (pinfunction "VCCINT1_P61") (pintype "passive"))
    )
    (net (code "53") (name "/VCC_B3") (class "Default")
      (node (ref "R11") (pin "2") (pinfunction "2_2") (pintype "passive"))
    )
    (net (code "54") (name "/X6") (class "Default")
      (node (ref "U1") (pin "P51") (pinfunction "IO_L31N_5D4_P51") (pintype "bidirectional"))
    )
    (net (code "57") (name "/XXCSYNC") (class "Default")
      (node (ref "U1") (pin "P137") (pinfunction "IO_L27N_0_P137") (pintype "bidirectional"))
    )
    (net (code "59") (name "GND") (class "Default")
      (node (ref "C1") (pin "1") (pinfunction "1_1") (pintype "passive"))
      (node (ref "C10") (pin "2") (pinfunction "2_2") (pintype "passive"))
      (node (ref "C11") (pin "2") (pinfunction "2_2") (pintype "passive"))
      (node (ref "C12") (pin "2") (pinfunction "2_2") (pintype "passive"))
      (node (ref "C13") (pin "2") (pinfunction "2_2") (pintype "passive"))
      (node (ref "C14") (pin "2") (pinfunction "2_2") (pintype "passive"))
      (node (ref "C15") (pin "2") (pinfunction "2_2") (pintype "passive"))
      (node (ref "C16") (pin "2") (pinfunction "2_2") (pintype "passive"))
      (node (ref "C17") (pin "2") (pinfunction "2_2") (pintype "passive"))
      (node (ref "C18") (pin "2") (pinfunction "2_2") (pintype "passive"))
      (node (ref "C19") (pin "2") (pinfunction "2_2") (pintype "passive"))
      (node (ref "C20") (pin "2") (pinfunction "2_2") (pintype "passive"))
      (node (ref "C21") (pin "2") (pinfunction "2_2") (pintype "passive"))
      (node (ref "C22") (pin "2") (pinfunction "2_2") (pintype "passive"))
      (node (ref "C23") (pin "2") (pinfunction "2_2") (pintype "passive"))
      (node (ref "C24") (pin "2") (pinfunction "2_2") (pintype "passive"))
      (node (ref "C25") (pin "2") (pinfunction "2_2") (pintype "passive"))
      (node (ref "C26") (pin "2") (pinfunction "2_2") (pintype "passive"))
      (node (ref "C27") (pin "2") (pinfunction "2_2") (pintype "passive"))
      (node (ref "C28") (pin "2") (pinfunction "2_2") (pintype "passive"))
      (node (ref "C29") (pin "2") (pinfunction "2_2") (pintype "passive"))
      (node (ref "C30") (pin "2") (pinfunction "2_2") (pintype "passive"))
      (node (ref "C31") (pin "2") (pinfunction "2_2") (pintype "passive"))
      (node (ref "C32") (pin "2") (pinfunction "2_2") (pintype "passive"))
      (node (ref "C33") (pin "-") (pinfunction "-_-") (pintype "passive"))
      (node (ref "C34") (pin "2") (pinfunction "2_2") (pintype "passive"))
      (node (ref "C35") (pin "-") (pinfunction "-_-") (pintype "passive"))
      (node (ref "C36") (pin "-") (pinfunction "-_-") (pintype "passive"))
      (node (ref "C5") (pin "1") (pinfunction "1_1") (pintype "passive"))
      (node (ref "C6") (pin "2") (pinfunction "2_2") (pintype "passive"))
      (node (ref "C7") (pin "2") (pinfunction "2_2") (pintype "passive"))
      (node (ref "C8") (pin "2") (pinfunction "2_2") (pintype "passive"))
      (node (ref "C9") (pin "2") (pinfunction "2_2") (pintype "passive"))
      (node (ref "IC1") (pin "11") (pinfunction "GND_11") (pintype "bidirectional"))
      (node (ref "IC2") (pin "4") (pinfunction "GND_4") (pintype "power_in"))
      (node (ref "IC3") (pin "3") (pinfunction "GND_3") (pintype "bidirectional"))
      (node (ref "JP3") (pin "6") (pinfunction "6_6") (pintype "passive"))
      (node (ref "R12") (pin "1") (pinfunction "1_1") (pintype "passive"))
      (node (ref "R17") (pin "1") (pinfunction "1_1") (pintype "passive"))
      (node (ref "R19") (pin "1") (pinfunction "1_1") (pintype "passive"))
      (node (ref "R21") (pin "1") (pinfunction "1_1") (pintype "passive"))
      (node (ref "REG1.2") (pin "1") (pinfunction "GND_1") (pintype "bidirectional"))
      (node (ref "REG2.5") (pin "1") (pinfunction "GND_1") (pintype "bidirectional"))
      (node (ref "RESET_SW") (pin "2") (pinfunction "2_2") (pintype "passive"))
      (node (ref "U$1") (pin "P24") (pinfunction "VSS_P24") (pintype "bidirectional"))
      (node (ref "U$1") (pin "P30") (pinfunction "CE_P30") (pintype "bidirectional"))
      (node (ref "U$2") (pin "GND") (pinfunction "GND_GND") (pintype "power_in"))
      (node (ref "U$4") (pin "1") (pinfunction "GND_1") (pintype "bidirectional"))
      (node (ref "U$5") (pin "1") (pinfunction "GND_1") (pintype "bidirectional"))
      (node (ref "U$6") (pin "P24") (pinfunction "VSS_P24") (pintype "bidirectional"))
      (node (ref "U$6") (pin "P30") (pinfunction "CE_P30") (pintype "bidirectional"))
      (node (ref "U1") (pin "P101") (pinfunction "GND11_P101") (pintype "passive"))
      (node (ref "U1") (pin "P114") (pinfunction "GND12_P114") (pintype "passive"))
      (node (ref "U1") (pin "P117") (pinfunction "GND13_P117") (pintype "passive"))
      (node (ref "U1") (pin "P136") (pinfunction "GND14_P136") (pintype "passive"))
      (node (ref "U1") (pin "P139") (pinfunction "GND15_P139") (pintype "passive"))
      (node (ref "U1") (pin "P16") (pinfunction "GND1_P16") (pintype "passive"))
      (node (ref "U1") (pin "P22") (pinfunction "GND2_P22") (pintype "passive"))
      (node (ref "U1") (pin "P29") (pinfunction "GND3_P29") (pintype "passive"))
      (node (ref "U1") (pin "P37") (pinfunction "M1_P37") (pintype "bidirectional"))
      (node (ref "U1") (pin "P38") (pinfunction "M0_P38") (pintype "bidirectional"))
      (node (ref "U1") (pin "P39") (pinfunction "M2_P39") (pintype "bidirectional"))
      (node (ref "U1") (pin "P42") (pinfunction "GND4_P42") (pintype "passive"))
      (node (ref "U1") (pin "P45") (pinfunction "GND5_P45") (pintype "passive"))
      (node (ref "U1") (pin "P64") (pinfunction "GND6_P64") (pintype "passive"))
      (node (ref "U1") (pin "P67") (pinfunction "GND7_P67") (pintype "passive"))
      (node (ref "U1") (pin "P81") (pinfunction "GND8_P81") (pintype "passive"))
      (node (ref "U1") (pin "P88") (pinfunction "GND9_P88") (pintype "passive"))
      (node (ref "U1") (pin "P9") (pinfunction "GND0_P9") (pintype "passive"))
      (node (ref "U1") (pin "P94") (pinfunction "GND10_P94") (pintype "passive"))
      (node (ref "X1") (pin "3") (pinfunction "2_3") (pintype "passive"))
      (node (ref "X2") (pin "13") (pinfunction "13_13") (pintype "passive"))
      (node (ref "X2") (pin "14") (pinfunction "14_14") (pintype "passive"))
      (node (ref "X2") (pin "17") (pinfunction "17_17") (pintype "passive"))
      (node (ref "X2") (pin "18") (pinfunction "18_18") (pintype "passive"))
      (node (ref "X2") (pin "21") (pinfunction "21_21") (pintype "passive"))
      (node (ref "X2") (pin "4") (pinfunction "4_4") (pintype "passive"))
      (node (ref "X2") (pin "5") (pinfunction "5_5") (pintype "passive"))
      (node (ref "X2") (pin "9") (pinfunction "9_9") (pintype "passive"))
      (node (ref "X3") (pin "3") (pinfunction "3_3") (pintype "passive"))
      (node (ref "X3") (pin "SH1") (pinfunction "PE1_SH1") (pintype "power_in"))
      (node (ref "X3") (pin "SH2") (pinfunction "PE2_SH2") (pintype "power_in"))
      (node (ref "X3") (pin "SH3") (pinfunction "PE3_SH3") (pintype "power_in"))
      (node (ref "X4") (pin "8") (pinfunction "F_8") (pintype "passive"))
      (node (ref "X4") (pin "G1") (pinfunction "G1_G1") (pintype "passive"))
      (node (ref "X5") (pin "8") (pinfunction "F_8") (pintype "passive"))
      (node (ref "X5") (pin "G1") (pinfunction "G1_G1") (pintype "passive"))
      (node (ref "X8") (pin "1") (pinfunction "1_1") (pintype "power_in"))
      (node (ref "X8") (pin "3") (pinfunction "3_3") (pintype "power_in"))
    )
    (net (code "60") (name "Net-(C1-Pad2)") (class "Default")
      (node (ref "C1") (pin "2") (pinfunction "2_2") (pintype "passive"))
      (node (ref "R23") (pin "2") (pinfunction "2_2") (pintype "passive"))
      (node (ref "R48") (pin "1") (pinfunction "1_1") (pintype "passive"))
    )
    (net (code "61") (name "Net-(C2-Pad1)") (class "Default")
      (node (ref "C2") (pin "1") (pinfunction "1_1") (pintype "passive"))
      (node (ref "R17") (pin "2") (pinfunction "2_2") (pintype "passive"))
      (node (ref "X1") (pin "1") (pinfunction "1_1") (pintype "passive"))
    )
    (net (code "62") (name "Net-(C3-Pad1)") (class "Default")
      (node (ref "C3") (pin "1") (pinfunction "1_1") (pintype "passive"))
      (node (ref "R48") (pin "2") (pinfunction "2_2") (pintype "passive"))
    )
    (net (code "63") (name "Net-(C4-Pad1)") (class "Default")
      (node (ref "C4") (pin "1") (pinfunction "1_1") (pintype "passive"))
      (node (ref "R49") (pin "2") (pinfunction "2_2") (pintype "passive"))
    )
    (net (code "64") (name "Net-(C5-Pad2)") (class "Default")
      (node (ref "C5") (pin "2") (pinfunction "2_2") (pintype "passive"))
      (node (ref "R34") (pin "2") (pinfunction "2_2") (pintype "passive"))
      (node (ref "R49") (pin "1") (pinfunction "1_1") (pintype "passive"))
    )
    (net (code "65") (name "Net-(IC1-CLK)") (class "Default")
      (node (ref "IC1") (pin "3") (pinfunction "CLK_3") (pintype "bidirectional"))
      (node (ref "U1") (pin "P72") (pinfunction "CCLK_P72") (pintype "bidirectional"))
    )
    (net (code "66") (name "Net-(IC1-TDI)") (class "Default")
      (node (ref "IC1") (pin "4") (pinfunction "TDI_4") (pintype "bidirectional"))
      (node (ref "U1") (pin "P109") (pinfunction "TDO_P109") (pintype "bidirectional"))
    )
    (net (code "67") (name "Net-(IC1-{slash}CE)") (class "Default")
      (node (ref "IC1") (pin "10") (pinfunction "/CE_10") (pintype "bidirectional"))
      (node (ref "U1") (pin "P71") (pinfunction "DONE_P71") (pintype "bidirectional"))
    )
    (net (code "68") (name "Net-(IC1-{slash}CF)") (class "Default")
      (node (ref "IC1") (pin "7") (pinfunction "/CF_7") (pintype "bidirectional"))
      (node (ref "U1") (pin "P143") (pinfunction "PROG_B_P143") (pintype "bidirectional"))
    )
    (net (code "69") (name "Net-(IC3-D+)") (class "Default")
      (node (ref "IC3") (pin "29") (pinfunction "D+_29") (pintype "bidirectional"))
      (node (ref "R54") (pin "2") (pinfunction "2_2") (pintype "passive"))
    )
    (net (code "70") (name "Net-(IC3-D-)") (class "Default")
      (node (ref "IC3") (pin "30") (pinfunction "D-_30") (pintype "bidirectional"))
      (node (ref "R53") (pin "2") (pinfunction "2_2") (pintype "passive"))
    )
    (net (code "71") (name "Net-(IC3-UGND)") (class "Default")
      (node (ref "IC3") (pin "28") (pinfunction "UGND_28") (pintype "bidirectional"))
      (node (ref "X6") (pin "4") (pinfunction "4_4") (pintype "passive"))
    )
    (net (code "72") (name "Net-(Q5-B)") (class "Default")
      (node (ref "Q5") (pin "1") (pinfunction "B_1") (pintype "passive"))
      (node (ref "R8") (pin "2") (pinfunction "2_2") (pintype "passive"))
    )
    (net (code "73") (name "Net-(Q5-E)") (class "Default")
      (node (ref "Q5") (pin "2") (pinfunction "E_2") (pintype "passive"))
      (node (ref "R13") (pin "2") (pinfunction "2_2") (pintype "passive"))
      (node (ref "R14") (pin "2") (pinfunction "2_2") (pintype "passive"))
    )
    (net (code "74") (name "Net-(Q6-B)") (class "Default")
      (node (ref "Q6") (pin "1") (pinfunction "B_1") (pintype "passive"))
      (node (ref "R10") (pin "2") (pinfunction "2_2") (pintype "passive"))
      (node (ref "R9") (pin "2") (pinfunction "2_2") (pintype "passive"))
    )
    (net (code "75") (name "Net-(Q6-E)") (class "Default")
      (node (ref "Q6") (pin "2") (pinfunction "E_2") (pintype "passive"))
      (node (ref "R15") (pin "2") (pinfunction "2_2") (pintype "passive"))
      (node (ref "R16") (pin "2") (pinfunction "2_2") (pintype "passive"))
      (node (ref "R20") (pin "2") (pinfunction "2_2") (pintype "passive"))
    )
    (net (code "76") (name "Net-(Q7-B)") (class "Default")
      (node (ref "Q7") (pin "1") (pinfunction "B_1") (pintype "passive"))
      (node (ref "R29") (pin "2") (pinfunction "2_2") (pintype "passive"))
      (node (ref "R30") (pin "2") (pinfunction "2_2") (pintype "passive"))
    )
    (net (code "77") (name "Net-(Q7-E)") (class "Default")
      (node (ref "Q7") (pin "2") (pinfunction "E_2") (pintype "passive"))
      (node (ref "R31") (pin "2") (pinfunction "2_2") (pintype "passive"))
      (node (ref "R32") (pin "2") (pinfunction "2_2") (pintype "passive"))
      (node (ref "R33") (pin "2") (pinfunction "2_2") (pintype "passive"))
    )
    (net (code "78") (name "Net-(Q8-B)") (class "Default")
      (node (ref "Q8") (pin "1") (pinfunction "B_1") (pintype "passive"))
      (node (ref "R24") (pin "2") (pinfunction "2_2") (pintype "passive"))
      (node (ref "R25") (pin "2") (pinfunction "2_2") (pintype "passive"))
    )
    (net (code "79") (name "Net-(Q8-E)") (class "Default")
      (node (ref "Q8") (pin "2") (pinfunction "E_2") (pintype "passive"))
      (node (ref "R26") (pin "2") (pinfunction "2_2") (pintype "passive"))
      (node (ref "R27") (pin "2") (pinfunction "2_2") (pintype "passive"))
      (node (ref "R28") (pin "2") (pinfunction "2_2") (pintype "passive"))
    )
    (net (code "80") (name "Net-(R18-Pad2)") (class "Default")
      (node (ref "R18") (pin "2") (pinfunction "2_2") (pintype "passive"))
      (node (ref "R22") (pin "2") (pinfunction "2_2") (pintype "passive"))
    )
    (net (code "81") (name "Net-(R53-Pad1)") (class "Default")
      (node (ref "R53") (pin "1") (pinfunction "1_1") (pintype "passive"))
      (node (ref "X6") (pin "2") (pinfunction "2_2") (pintype "passive"))
    )
    (net (code "82") (name "Net-(R54-Pad1)") (class "Default")
      (node (ref "R54") (pin "1") (pinfunction "1_1") (pintype "passive"))
      (node (ref "X6") (pin "3") (pinfunction "3_3") (pintype "passive"))
    )
    (net (code "83") (name "Net-(T2-B)") (class "Default")
      (node (ref "C2") (pin "2") (pinfunction "2_2") (pintype "passive"))
      (node (ref "R18") (pin "1") (pinfunction "1_1") (pintype "passive"))
      (node (ref "R19") (pin "2") (pinfunction "2_2") (pintype "passive"))
      (node (ref "T2") (pin "1") (pinfunction "B_1") (pintype "passive"))
    )
    (net (code "84") (name "Net-(U$1-A0)") (class "Default")
      (node (ref "U$1") (pin "P20") (pinfunction "A0_P20") (pintype "bidirectional"))
      (node (ref "U1") (pin "P77") (pinfunction "IO_L20P_3_P77") (pintype "bidirectional"))
    )
    (net (code "85") (name "Net-(U$1-A1)") (class "Default")
      (node (ref "U$1") (pin "P19") (pinfunction "A1_P19") (pintype "bidirectional"))
      (node (ref "U1") (pin "P76") (pinfunction "IO_P76") (pintype "bidirectional"))
    )
    (net (code "86") (name "Net-(U$1-A2)") (class "Default")
      (node (ref "U$1") (pin "P18") (pinfunction "A2_P18") (pintype "bidirectional"))
      (node (ref "U1") (pin "P74") (pinfunction "IO_L01N_3VRP_3_P74") (pintype "bidirectional"))
    )
    (net (code "87") (name "Net-(U$1-A3)") (class "Default")
      (node (ref "U$1") (pin "P17") (pinfunction "A3_P17") (pintype "bidirectional"))
      (node (ref "U1") (pin "P73") (pinfunction "IO_L01P_3VRN_3_P73") (pintype "bidirectional"))
    )
    (net (code "88") (name "Net-(U$1-A4)") (class "Default")
      (node (ref "U$1") (pin "P16") (pinfunction "A4_P16") (pintype "bidirectional"))
      (node (ref "U1") (pin "P108") (pinfunction "IO_L01N_2VRP_2_P108") (pintype "bidirectional"))
    )
    (net (code "89") (name "Net-(U$1-A5)") (class "Default")
      (node (ref "U$1") (pin "P15") (pinfunction "A5_P15") (pintype "bidirectional"))
      (node (ref "U1") (pin "P107") (pinfunction "IO_L01P_2VRN_2_P107") (pintype "bidirectional"))
    )
    (net (code "90") (name "Net-(U$1-A6)") (class "Default")
      (node (ref "U$1") (pin "P14") (pinfunction "A6_P14") (pintype "bidirectional"))
      (node (ref "U1") (pin "P105") (pinfunction "IO_L20N_2_P105") (pintype "bidirectional"))
    )
    (net (code "91") (name "Net-(U$1-A7)") (class "Default")
      (node (ref "U$1") (pin "P13") (pinfunction "A7_P13") (pintype "bidirectional"))
      (node (ref "U1") (pin "P104") (pinfunction "IO_L20P_2_P104") (pintype "bidirectional"))
    )
    (net (code "92") (name "Net-(U$1-A8)") (class "Default")
      (node (ref "U$1") (pin "P3") (pinfunction "A8_P3") (pintype "bidirectional"))
      (node (ref "U1") (pin "P93") (pinfunction "IO_L40N_2_P93") (pintype "bidirectional"))
    )
    (net (code "93") (name "Net-(U$1-A9)") (class "Default")
      (node (ref "U$1") (pin "P2") (pinfunction "A9_P2") (pintype "bidirectional"))
      (node (ref "U1") (pin "P92") (pinfunction "IO_L40P_2VREF_2_P92") (pintype "bidirectional"))
    )
    (net (code "94") (name "Net-(U$1-A10)") (class "Default")
      (node (ref "U$1") (pin "P31") (pinfunction "A10_P31") (pintype "bidirectional"))
      (node (ref "U1") (pin "P87") (pinfunction "IO_L24N_3_P87") (pintype "bidirectional"))
    )
    (net (code "95") (name "Net-(U$1-A11)") (class "Default")
      (node (ref "U$1") (pin "P1") (pinfunction "A11_P1") (pintype "bidirectional"))
      (node (ref "U1") (pin "P90") (pinfunction "IO_L40N_3VREF_3_P90") (pintype "bidirectional"))
    )
    (net (code "96") (name "Net-(U$1-A12)") (class "Default")
      (node (ref "U$1") (pin "P12") (pinfunction "A12_P12") (pintype "bidirectional"))
      (node (ref "U1") (pin "P103") (pinfunction "IO_L21N_2_P103") (pintype "bidirectional"))
    )
    (net (code "97") (name "Net-(U$1-A13)") (class "Default")
      (node (ref "U$1") (pin "P4") (pinfunction "A13_P4") (pintype "bidirectional"))
      (node (ref "U1") (pin "P95") (pinfunction "IO_L24P_2_P95") (pintype "bidirectional"))
    )
    (net (code "98") (name "Net-(U$1-A14)") (class "Default")
      (node (ref "U$1") (pin "P11") (pinfunction "A14_P11") (pintype "bidirectional"))
      (node (ref "U1") (pin "P102") (pinfunction "IO_L21P_2_P102") (pintype "bidirectional"))
    )
    (net (code "99") (name "Net-(U$1-A15)") (class "Default")
      (node (ref "U$1") (pin "P7") (pinfunction "A15_P7") (pintype "bidirectional"))
      (node (ref "U1") (pin "P98") (pinfunction "IO_L23N_2VREF_2_P98") (pintype "bidirectional"))
    )
    (net (code "100") (name "Net-(U$1-A16)") (class "Default")
      (node (ref "U$1") (pin "P10") (pinfunction "A16_P10") (pintype "bidirectional"))
      (node (ref "U1") (pin "P100") (pinfunction "IO_L22N_2_P100") (pintype "bidirectional"))
    )
    (net (code "101") (name "Net-(U$1-A17)") (class "Default")
      (node (ref "U$1") (pin "P6") (pinfunction "A17_P6") (pintype "bidirectional"))
      (node (ref "U1") (pin "P97") (pinfunction "IO_L23P_2_P97") (pintype "bidirectional"))
    )
    (net (code "102") (name "Net-(U$1-A18)") (class "Default")
      (node (ref "U$1") (pin "P9") (pinfunction "A18_P9") (pintype "bidirectional"))
      (node (ref "U1") (pin "P99") (pinfunction "IO_L22P_2_P99") (pintype "bidirectional"))
    )
    (net (code "103") (name "Net-(U$1-DQ0)") (class "Default")
      (node (ref "U$1") (pin "P21") (pinfunction "DQ0_P21") (pintype "bidirectional"))
      (node (ref "U1") (pin "P78") (pinfunction "IO_L20N_3_P78") (pintype "bidirectional"))
    )
    (net (code "104") (name "Net-(U$1-DQ1)") (class "Default")
      (node (ref "U$1") (pin "P22") (pinfunction "DQ1_P22") (pintype "bidirectional"))
      (node (ref "U1") (pin "P79") (pinfunction "IO_L21P_3_P79") (pintype "bidirectional"))
    )
    (net (code "105") (name "Net-(U$1-DQ2)") (class "Default")
      (node (ref "U$1") (pin "P23") (pinfunction "DQ2_P23") (pintype "bidirectional"))
      (node (ref "U1") (pin "P80") (pinfunction "IO_L21N_3_P80") (pintype "bidirectional"))
    )
    (net (code "106") (name "Net-(U$1-DQ3)") (class "Default")
      (node (ref "U$1") (pin "P25") (pinfunction "DQ3_P25") (pintype "bidirectional"))
      (node (ref "U1") (pin "P82") (pinfunction "IO_L22P_3_P82") (pintype "bidirectional"))
    )
    (net (code "107") (name "Net-(U$1-DQ4)") (class "Default")
      (node (ref "U$1") (pin "P26") (pinfunction "DQ4_P26") (pintype "bidirectional"))
      (node (ref "U1") (pin "P83") (pinfunction "IO_L22N_3_P83") (pintype "bidirectional"))
    )
    (net (code "108") (name "Net-(U$1-DQ5)") (class "Default")
      (node (ref "U$1") (pin "P27") (pinfunction "DQ5_P27") (pintype "bidirectional"))
      (node (ref "U1") (pin "P84") (pinfunction "IO_L23P_3VREF_3_P84") (pintype "bidirectional"))
    )
    (net (code "109") (name "Net-(U$1-DQ6)") (class "Default")
      (node (ref "U$1") (pin "P28") (pinfunction "DQ6_P28") (pintype "bidirectional"))
      (node (ref "U1") (pin "P85") (pinfunction "IO_L23N_3_P85") (pintype "bidirectional"))
    )
    (net (code "110") (name "Net-(U$1-DQ7)") (class "Default")
      (node (ref "U$1") (pin "P29") (pinfunction "DQ7_P29") (pintype "bidirectional"))
      (node (ref "U1") (pin "P86") (pinfunction "IO_L24P_3_P86") (pintype "bidirectional"))
    )
    (net (code "111") (name "Net-(U$1-OE)") (class "Default")
      (node (ref "U$1") (pin "P32") (pinfunction "OE_P32") (pintype "bidirectional"))
      (node (ref "U1") (pin "P89") (pinfunction "IO_L40P_3_P89") (pintype "bidirectional"))
    )
    (net (code "112") (name "Net-(U$1-WE)") (class "Default")
      (node (ref "U$1") (pin "P5") (pinfunction "WE_P5") (pintype "bidirectional"))
      (node (ref "U1") (pin "P96") (pinfunction "IO_L24N_2_P96") (pintype "bidirectional"))
    )
    (net (code "113") (name "Net-(U$6-A0)") (class "Default")
      (node (ref "U$6") (pin "P20") (pinfunction "A0_P20") (pintype "bidirectional"))
      (node (ref "U1") (pin "P24") (pinfunction "IO_L24N_6VREF_6_P24") (pintype "bidirectional"))
    )
    (net (code "114") (name "Net-(U$6-A1)") (class "Default")
      (node (ref "U$6") (pin "P19") (pinfunction "A1_P19") (pintype "bidirectional"))
      (node (ref "U1") (pin "P23") (pinfunction "IO_L24P_6_P23") (pintype "bidirectional"))
    )
    (net (code "115") (name "Net-(U$6-A2)") (class "Default")
      (node (ref "U$6") (pin "P18") (pinfunction "A2_P18") (pintype "bidirectional"))
      (node (ref "U1") (pin "P21") (pinfunction "IO_L40N_6_P21") (pintype "bidirectional"))
    )
    (net (code "116") (name "Net-(U$6-A3)") (class "Default")
      (node (ref "U$6") (pin "P17") (pinfunction "A3_P17") (pintype "bidirectional"))
      (node (ref "U1") (pin "P20") (pinfunction "IO_L40P_6VREF_6_P20") (pintype "bidirectional"))
    )
    (net (code "117") (name "Net-(U$6-A4)") (class "Default")
      (node (ref "U$6") (pin "P16") (pinfunction "A4_P16") (pintype "bidirectional"))
      (node (ref "U1") (pin "P18") (pinfunction "IO_L40N_7VREF_7_P18") (pintype "bidirectional"))
    )
    (net (code "118") (name "Net-(U$6-A5)") (class "Default")
      (node (ref "U$6") (pin "P15") (pinfunction "A5_P15") (pintype "bidirectional"))
      (node (ref "U1") (pin "P17") (pinfunction "IO_L40P_7_P17") (pintype "bidirectional"))
    )
    (net (code "119") (name "Net-(U$6-A6)") (class "Default")
      (node (ref "U$6") (pin "P14") (pinfunction "A6_P14") (pintype "bidirectional"))
      (node (ref "U1") (pin "P15") (pinfunction "IO_L24N_7_P15") (pintype "bidirectional"))
    )
    (net (code "120") (name "Net-(U$6-A7)") (class "Default")
      (node (ref "U$6") (pin "P13") (pinfunction "A7_P13") (pintype "bidirectional"))
      (node (ref "U1") (pin "P14") (pinfunction "IO_L24P_7_P14") (pintype "bidirectional"))
    )
    (net (code "121") (name "Net-(U$6-A8)") (class "Default")
      (node (ref "U$6") (pin "P3") (pinfunction "A8_P3") (pintype "bidirectional"))
      (node (ref "U1") (pin "P4") (pinfunction "IOVREF_7_P4") (pintype "bidirectional"))
    )
    (net (code "122") (name "Net-(U$6-A9)") (class "Default")
      (node (ref "U$6") (pin "P2") (pinfunction "A9_P2") (pintype "bidirectional"))
      (node (ref "U1") (pin "P2") (pinfunction "IO_L01N_7VRP_7_P2") (pintype "bidirectional"))
    )
    (net (code "123") (name "Net-(U$6-A10)") (class "Default")
      (node (ref "U$6") (pin "P31") (pinfunction "A10_P31") (pintype "bidirectional"))
      (node (ref "U1") (pin "P35") (pinfunction "IO_L01P_6VRN_6_P35") (pintype "bidirectional"))
    )
    (net (code "124") (name "Net-(U$6-A11)") (class "Default")
      (node (ref "U$6") (pin "P1") (pinfunction "A11_P1") (pintype "bidirectional"))
      (node (ref "U1") (pin "P1") (pinfunction "IO_L01P_7VRN_7_P1") (pintype "bidirectional"))
    )
    (net (code "125") (name "Net-(U$6-A12)") (class "Default")
      (node (ref "U$6") (pin "P12") (pinfunction "A12_P12") (pintype "bidirectional"))
      (node (ref "U1") (pin "P13") (pinfunction "IO_L23N_7_P13") (pintype "bidirectional"))
    )
    (net (code "126") (name "Net-(U$6-A13)") (class "Default")
      (node (ref "U$6") (pin "P4") (pinfunction "A13_P4") (pintype "bidirectional"))
      (node (ref "U1") (pin "P5") (pinfunction "IO_L20P_7_P5") (pintype "bidirectional"))
    )
    (net (code "127") (name "Net-(U$6-A14)") (class "Default")
      (node (ref "U$6") (pin "P11") (pinfunction "A14_P11") (pintype "bidirectional"))
      (node (ref "U1") (pin "P12") (pinfunction "IO_L23P_7_P12") (pintype "bidirectional"))
    )
    (net (code "128") (name "Net-(U$6-A15)") (class "Default")
      (node (ref "U$6") (pin "P7") (pinfunction "A15_P7") (pintype "bidirectional"))
      (node (ref "U1") (pin "P8") (pinfunction "IO_L21N_7_P8") (pintype "bidirectional"))
    )
    (net (code "129") (name "Net-(U$6-A16)") (class "Default")
      (node (ref "U$6") (pin "P10") (pinfunction "A16_P10") (pintype "bidirectional"))
      (node (ref "U1") (pin "P11") (pinfunction "IO_L22N_7_P11") (pintype "bidirectional"))
    )
    (net (code "130") (name "Net-(U$6-A17)") (class "Default")
      (node (ref "U$6") (pin "P6") (pinfunction "A17_P6") (pintype "bidirectional"))
      (node (ref "U1") (pin "P7") (pinfunction "IO_L21P_7_P7") (pintype "bidirectional"))
    )
    (net (code "131") (name "Net-(U$6-A18)") (class "Default")
      (node (ref "U$6") (pin "P9") (pinfunction "A18_P9") (pintype "bidirectional"))
      (node (ref "U1") (pin "P10") (pinfunction "IO_L22P_7_P10") (pintype "bidirectional"))
    )
    (net (code "132") (name "Net-(U$6-DQ0)") (class "Default")
      (node (ref "U$6") (pin "P21") (pinfunction "DQ0_P21") (pintype "bidirectional"))
      (node (ref "U1") (pin "P25") (pinfunction "IO_L23P_6_P25") (pintype "bidirectional"))
    )
    (net (code "133") (name "Net-(U$6-DQ1)") (class "Default")
      (node (ref "U$6") (pin "P22") (pinfunction "DQ1_P22") (pintype "bidirectional"))
      (node (ref "U1") (pin "P26") (pinfunction "IO_L23N_6_P26") (pintype "bidirectional"))
    )
    (net (code "134") (name "Net-(U$6-DQ2)") (class "Default")
      (node (ref "U$6") (pin "P23") (pinfunction "DQ2_P23") (pintype "bidirectional"))
      (node (ref "U1") (pin "P27") (pinfunction "IO_L22P_6_P27") (pintype "bidirectional"))
    )
    (net (code "135") (name "Net-(U$6-DQ3)") (class "Default")
      (node (ref "U$6") (pin "P25") (pinfunction "DQ3_P25") (pintype "bidirectional"))
      (node (ref "U1") (pin "P28") (pinfunction "IO_L22N_6_P28") (pintype "bidirectional"))
    )
    (net (code "136") (name "Net-(U$6-DQ4)") (class "Default")
      (node (ref "U$6") (pin "P26") (pinfunction "DQ4_P26") (pintype "bidirectional"))
      (node (ref "U1") (pin "P30") (pinfunction "IO_L21P_6_P30") (pintype "bidirectional"))
    )
    (net (code "137") (name "Net-(U$6-DQ5)") (class "Default")
      (node (ref "U$6") (pin "P27") (pinfunction "DQ5_P27") (pintype "bidirectional"))
      (node (ref "U1") (pin "P31") (pinfunction "IO_L21N_6_P31") (pintype "bidirectional"))
    )
    (net (code "138") (name "Net-(U$6-DQ6)") (class "Default")
      (node (ref "U$6") (pin "P28") (pinfunction "DQ6_P28") (pintype "bidirectional"))
      (node (ref "U1") (pin "P32") (pinfunction "IO_L20P_6_P32") (pintype "bidirectional"))
    )
    (net (code "139") (name "Net-(U$6-DQ7)") (class "Default")
      (node (ref "U$6") (pin "P29") (pinfunction "DQ7_P29") (pintype "bidirectional"))
      (node (ref "U1") (pin "P33") (pinfunction "IO_L20N_6_P33") (pintype "bidirectional"))
    )
    (net (code "140") (name "Net-(U$6-OE)") (class "Default")
      (node (ref "U$6") (pin "P32") (pinfunction "OE_P32") (pintype "bidirectional"))
      (node (ref "U1") (pin "P36") (pinfunction "IO_L01N_6VRP_6_P36") (pintype "bidirectional"))
    )
    (net (code "141") (name "Net-(U$6-WE)") (class "Default")
      (node (ref "U$6") (pin "P5") (pinfunction "WE_P5") (pintype "bidirectional"))
      (node (ref "U1") (pin "P6") (pinfunction "IO_L20N_7_P6") (pintype "bidirectional"))
    )
    (net (code "142") (name "Net-(U1N-TCK)") (class "Default")
      (node (ref "R2") (pin "1") (pinfunction "1_1") (pintype "passive"))
      (node (ref "U1") (pin "P110") (pinfunction "TCK_P110") (pintype "bidirectional"))
    )
    (net (code "143") (name "Net-(U1N-TDI)") (class "Default")
      (node (ref "R1") (pin "1") (pinfunction "1_1") (pintype "passive"))
      (node (ref "U1") (pin "P144") (pinfunction "TDI_P144") (pintype "bidirectional"))
    )
    (net (code "144") (name "Net-(U1N-TMS)") (class "Default")
      (node (ref "R3") (pin "1") (pinfunction "1_1") (pintype "passive"))
      (node (ref "U1") (pin "P111") (pinfunction "TMS_P111") (pintype "bidirectional"))
    )
    (net (code "145") (name "Net-(X4A-F)") (class "Default")
      (node (ref "R40") (pin "2") (pinfunction "2_2") (pintype "passive"))
      (node (ref "X4") (pin "1") (pinfunction "F_1") (pintype "passive"))
    )
    (net (code "146") (name "Net-(X4B-F)") (class "Default")
      (node (ref "R41") (pin "2") (pinfunction "2_2") (pintype "passive"))
      (node (ref "X4") (pin "2") (pinfunction "F_2") (pintype "passive"))
    )
    (net (code "147") (name "Net-(X4C-F)") (class "Default")
      (node (ref "R42") (pin "2") (pinfunction "2_2") (pintype "passive"))
      (node (ref "X4") (pin "3") (pinfunction "F_3") (pintype "passive"))
    )
    (net (code "148") (name "Net-(X4D-F)") (class "Default")
      (node (ref "R43") (pin "2") (pinfunction "2_2") (pintype "passive"))
      (node (ref "X4") (pin "4") (pinfunction "F_4") (pintype "passive"))
    )
    (net (code "149") (name "Net-(X4F-F)") (class "Default")
      (node (ref "R44") (pin "2") (pinfunction "2_2") (pintype "passive"))
      (node (ref "X4") (pin "6") (pinfunction "F_6") (pintype "passive"))
    )
    (net (code "150") (name "Net-(X4G-F)") (class "Default")
      (node (ref "R45") (pin "2") (pinfunction "2_2") (pintype "passive"))
      (node (ref "X4") (pin "7") (pinfunction "F_7") (pintype "passive"))
    )
    (net (code "151") (name "Net-(X5A-F)") (class "Default")
      (node (ref "R46") (pin "1") (pinfunction "1_1") (pintype "passive"))
      (node (ref "X5") (pin "1") (pinfunction "F_1") (pintype "passive"))
    )
    (net (code "152") (name "Net-(X5B-F)") (class "Default")
      (node (ref "R39") (pin "1") (pinfunction "1_1") (pintype "passive"))
      (node (ref "X5") (pin "2") (pinfunction "F_2") (pintype "passive"))
    )
    (net (code "153") (name "Net-(X5C-F)") (class "Default")
      (node (ref "R38") (pin "1") (pinfunction "1_1") (pintype "passive"))
      (node (ref "X5") (pin "3") (pinfunction "F_3") (pintype "passive"))
    )
    (net (code "154") (name "Net-(X5D-F)") (class "Default")
      (node (ref "R37") (pin "1") (pinfunction "1_1") (pintype "passive"))
      (node (ref "X5") (pin "4") (pinfunction "F_4") (pintype "passive"))
    )
    (net (code "155") (name "Net-(X5F-F)") (class "Default")
      (node (ref "R36") (pin "1") (pinfunction "1_1") (pintype "passive"))
      (node (ref "X5") (pin "6") (pinfunction "F_6") (pintype "passive"))
    )
    (net (code "156") (name "Net-(X5G-F)") (class "Default")
      (node (ref "R35") (pin "1") (pinfunction "1_1") (pintype "passive"))
      (node (ref "X5") (pin "7") (pinfunction "F_7") (pintype "passive"))
    )
    (net (code "157") (name "unconnected-(IC1-NC.1-Pad2)") (class "Default")
      (node (ref "IC1") (pin "2") (pinfunction "NC.1_2") (pintype "bidirectional"))
    )
    (net (code "158") (name "unconnected-(IC1-NC.2-Pad9)") (class "Default")
      (node (ref "IC1") (pin "9") (pinfunction "NC.2_9") (pintype "bidirectional"))
    )
    (net (code "159") (name "unconnected-(IC1-NC.3-Pad12)") (class "Default")
      (node (ref "IC1") (pin "12") (pinfunction "NC.3_12") (pintype "bidirectional"))
    )
    (net (code "160") (name "unconnected-(IC1-NC.4-Pad14)") (class "Default")
      (node (ref "IC1") (pin "14") (pinfunction "NC.4_14") (pintype "bidirectional"))
    )
    (net (code "161") (name "unconnected-(IC1-NC.5-Pad15)") (class "Default")
      (node (ref "IC1") (pin "15") (pinfunction "NC.5_15") (pintype "bidirectional"))
    )
    (net (code "162") (name "unconnected-(IC1-NC.6-Pad16)") (class "Default")
      (node (ref "IC1") (pin "16") (pinfunction "NC.6_16") (pintype "bidirectional"))
    )
    (net (code "163") (name "unconnected-(IC1-{slash}CEO-Pad13)") (class "Default")
      (node (ref "IC1") (pin "13") (pinfunction "/CEO_13") (pintype "bidirectional"))
    )
    (net (code "164") (name "unconnected-(IC3-PC2(AIN2{slash}PCIN11)-Pad5)") (class "Default")
      (node (ref "IC3") (pin "5") (pinfunction "PC2(AIN2/PCIN11)_5") (pintype "bidirectional"))
    )
    (net (code "165") (name "unconnected-(IC3-PC4(PCINT10)-Pad26)") (class "Default")
      (node (ref "IC3") (pin "26") (pinfunction "PC4(PCINT10)_26") (pintype "bidirectional"))
    )
    (net (code "166") (name "unconnected-(IC3-PC5(OC1B{slash}PCINT9)-Pad25)") (class "Default")
      (node (ref "IC3") (pin "25") (pinfunction "PC5(OC1B/PCINT9)_25") (pintype "bidirectional"))
    )
    (net (code "167") (name "unconnected-(IC3-PC6(OC1A{slash}PCINT8)-Pad23)") (class "Default")
      (node (ref "IC3") (pin "23") (pinfunction "PC6(OC1A/PCINT8)_23") (pintype "bidirectional"))
    )
    (net (code "168") (name "unconnected-(IC3-PD0(INT0{slash}OC0B)-Pad6)") (class "Default")
      (node (ref "IC3") (pin "6") (pinfunction "PD0(INT0/OC0B)_6") (pintype "bidirectional"))
    )
    (net (code "169") (name "unconnected-(IC3-PD1(INT1{slash}AIN0)-Pad7)") (class "Default")
      (node (ref "IC3") (pin "7") (pinfunction "PD1(INT1/AIN0)_7") (pintype "bidirectional"))
    )
    (net (code "170") (name "unconnected-(IC3-PD4(INT5{slash}AIN3)-Pad10)") (class "Default")
      (node (ref "IC3") (pin "10") (pinfunction "PD4(INT5/AIN3)_10") (pintype "bidirectional"))
    )
    (net (code "171") (name "unconnected-(IC3-PD5(XCK{slash}AIN4{slash}PCINT12)-Pad11)") (class "Default")
      (node (ref "IC3") (pin "11") (pinfunction "PD5(XCK/AIN4/PCINT12)_11") (pintype "bidirectional"))
    )
    (net (code "172") (name "unconnected-(IC3-PD6(INT6{slash}AIN5{slash}RTS)-Pad12)") (class "Default")
      (node (ref "IC3") (pin "12") (pinfunction "PD6(INT6/AIN5/RTS)_12") (pintype "bidirectional"))
    )
    (net (code "173") (name "unconnected-(IC3-UCAP-Pad27)") (class "Default")
      (node (ref "IC3") (pin "27") (pinfunction "UCAP_27") (pintype "bidirectional"))
    )
    (net (code "174") (name "unconnected-(IC3-XTAL1-Pad1)") (class "Default")
      (node (ref "IC3") (pin "1") (pinfunction "XTAL1_1") (pintype "bidirectional"))
    )
    (net (code "175") (name "unconnected-(IC3-XTAL2{slash}PC0-Pad2)") (class "Default")
      (node (ref "IC3") (pin "2") (pinfunction "XTAL2/PC0_2") (pintype "bidirectional"))
    )
    (net (code "176") (name "unconnected-(IC3-{slash}RESET(PC1)-Pad24)") (class "Default")
      (node (ref "IC3") (pin "24") (pinfunction "/RESET(PC1)_24") (pintype "bidirectional"))
    )
    (net (code "177") (name "unconnected-(REG1.2-VOUT2-Pad2)") (class "Default")
      (node (ref "REG1.2") (pin "2") (pinfunction "VOUT2_2") (pintype "bidirectional"))
    )
    (net (code "178") (name "unconnected-(REG2.5-VOUT2-Pad2)") (class "Default")
      (node (ref "REG2.5") (pin "2") (pinfunction "VOUT2_2") (pintype "bidirectional"))
    )
    (net (code "179") (name "unconnected-(U$2-TRI-PadENA)") (class "Default")
      (node (ref "U$2") (pin "ENA") (pinfunction "TRI_ENA") (pintype "input"))
    )
    (net (code "180") (name "unconnected-(U$4-VOUT2-Pad2)") (class "Default")
      (node (ref "U$4") (pin "2") (pinfunction "VOUT2_2") (pintype "bidirectional"))
    )
    (net (code "181") (name "unconnected-(U1A-IO_L27P_0-PadP135)") (class "Default")
      (node (ref "U1") (pin "P135") (pinfunction "IO_L27P_0_P135") (pintype "bidirectional"))
    )
    (net (code "182") (name "unconnected-(U1A-IO_L30N_0-PadP132)") (class "Default")
      (node (ref "U1") (pin "P132") (pinfunction "IO_L30N_0_P132") (pintype "bidirectional"))
    )
    (net (code "183") (name "unconnected-(U1A-IO_L30P_0-PadP131)") (class "Default")
      (node (ref "U1") (pin "P131") (pinfunction "IO_L30P_0_P131") (pintype "bidirectional"))
    )
    (net (code "184") (name "unconnected-(U1A-IO_L31N_0-PadP130)") (class "Default")
      (node (ref "U1") (pin "P130") (pinfunction "IO_L31N_0_P130") (pintype "bidirectional"))
    )
    (net (code "185") (name "unconnected-(U1A-IO_L31P_0VREF_0-PadP129)") (class "Default")
      (node (ref "U1") (pin "P129") (pinfunction "IO_L31P_0VREF_0_P129") (pintype "bidirectional"))
    )
    (net (code "186") (name "unconnected-(U1A-IO_L32N_0GCLK7-PadP128)") (class "Default")
      (node (ref "U1") (pin "P128") (pinfunction "IO_L32N_0GCLK7_P128") (pintype "bidirectional"))
    )
    (net (code "187") (name "unconnected-(U1A-IO_L32P_0GCLK6-PadP127)") (class "Default")
      (node (ref "U1") (pin "P127") (pinfunction "IO_L32P_0GCLK6_P127") (pintype "bidirectional"))
    )
    (net (code "188") (name "unconnected-(U1C-IO-PadP116)") (class "Default")
      (node (ref "U1") (pin "P116") (pinfunction "IO_P116") (pintype "bidirectional"))
    )
    (net (code "189") (name "unconnected-(U1C-IO_L01N_1VRP_1-PadP113)") (class "Default")
      (node (ref "U1") (pin "P113") (pinfunction "IO_L01N_1VRP_1_P113") (pintype "bidirectional"))
    )
    (net (code "190") (name "unconnected-(U1C-IO_L01P_1VRN_1-PadP112)") (class "Default")
      (node (ref "U1") (pin "P112") (pinfunction "IO_L01P_1VRN_1_P112") (pintype "bidirectional"))
    )
    (net (code "191") (name "unconnected-(U1C-IO_L28N_1-PadP119)") (class "Default")
      (node (ref "U1") (pin "P119") (pinfunction "IO_L28N_1_P119") (pintype "bidirectional"))
    )
    (net (code "192") (name "unconnected-(U1C-IO_L28P_1-PadP118)") (class "Default")
      (node (ref "U1") (pin "P118") (pinfunction "IO_L28P_1_P118") (pintype "bidirectional"))
    )
    (net (code "193") (name "unconnected-(U1C-IO_L31N_1VREF_1-PadP123)") (class "Default")
      (node (ref "U1") (pin "P123") (pinfunction "IO_L31N_1VREF_1_P123") (pintype "bidirectional"))
    )
    (net (code "194") (name "unconnected-(U1C-IO_L31P_1-PadP122)") (class "Default")
      (node (ref "U1") (pin "P122") (pinfunction "IO_L31P_1_P122") (pintype "bidirectional"))
    )
    (net (code "195") (name "unconnected-(U1C-IO_L32N_1GCLK5-PadP125)") (class "Default")
      (node (ref "U1") (pin "P125") (pinfunction "IO_L32N_1GCLK5_P125") (pintype "bidirectional"))
    )
    (net (code "196") (name "unconnected-(U1C-IO_L32P_1GCLK4-PadP124)") (class "Default")
      (node (ref "U1") (pin "P124") (pinfunction "IO_L32P_1GCLK4_P124") (pintype "bidirectional"))
    )
    (net (code "197") (name "unconnected-(U1N-HSWAP_EN-PadP142)") (class "Default")
      (node (ref "U1") (pin "P142") (pinfunction "HSWAP_EN_P142") (pintype "bidirectional"))
    )
    (net (code "198") (name "unconnected-(X1-3-Pad2)") (class "Default")
      (node (ref "X1") (pin "2") (pinfunction "3_2") (pintype "passive"))
    )
    (net (code "199") (name "unconnected-(X2-Pad10)") (class "Default")
      (node (ref "X2") (pin "10") (pinfunction "10_10") (pintype "passive"))
    )
    (net (code "200") (name "unconnected-(X2-Pad12)") (class "Default")
      (node (ref "X2") (pin "12") (pinfunction "12_12") (pintype "passive"))
    )
    (net (code "201") (name "unconnected-(X3-Pad2)") (class "Default")
      (node (ref "X3") (pin "2") (pinfunction "2_2") (pintype "passive"))
    )
    (net (code "202") (name "unconnected-(X3-Pad8)") (class "Default")
      (node (ref "X3") (pin "8") (pinfunction "8_8") (pintype "passive"))
    )
    (net (code "203") (name "unconnected-(X4-PadG2)") (class "Default")
      (node (ref "X4") (pin "G2") (pinfunction "G2_G2") (pintype "passive"))
    )
    (net (code "204") (name "unconnected-(X5-PadG2)") (class "Default")
      (node (ref "X5") (pin "G2") (pinfunction "G2_G2") (pintype "passive"))
    )
    (net (code "205") (name "unconnected-(X6-Pad1)") (class "Default")
      (node (ref "X6") (pin "1") (pinfunction "1_1") (pintype "passive"))
    )
  )
)
